# ImageProc.net
KiCad netlist of a schematic drawn in EAGLE
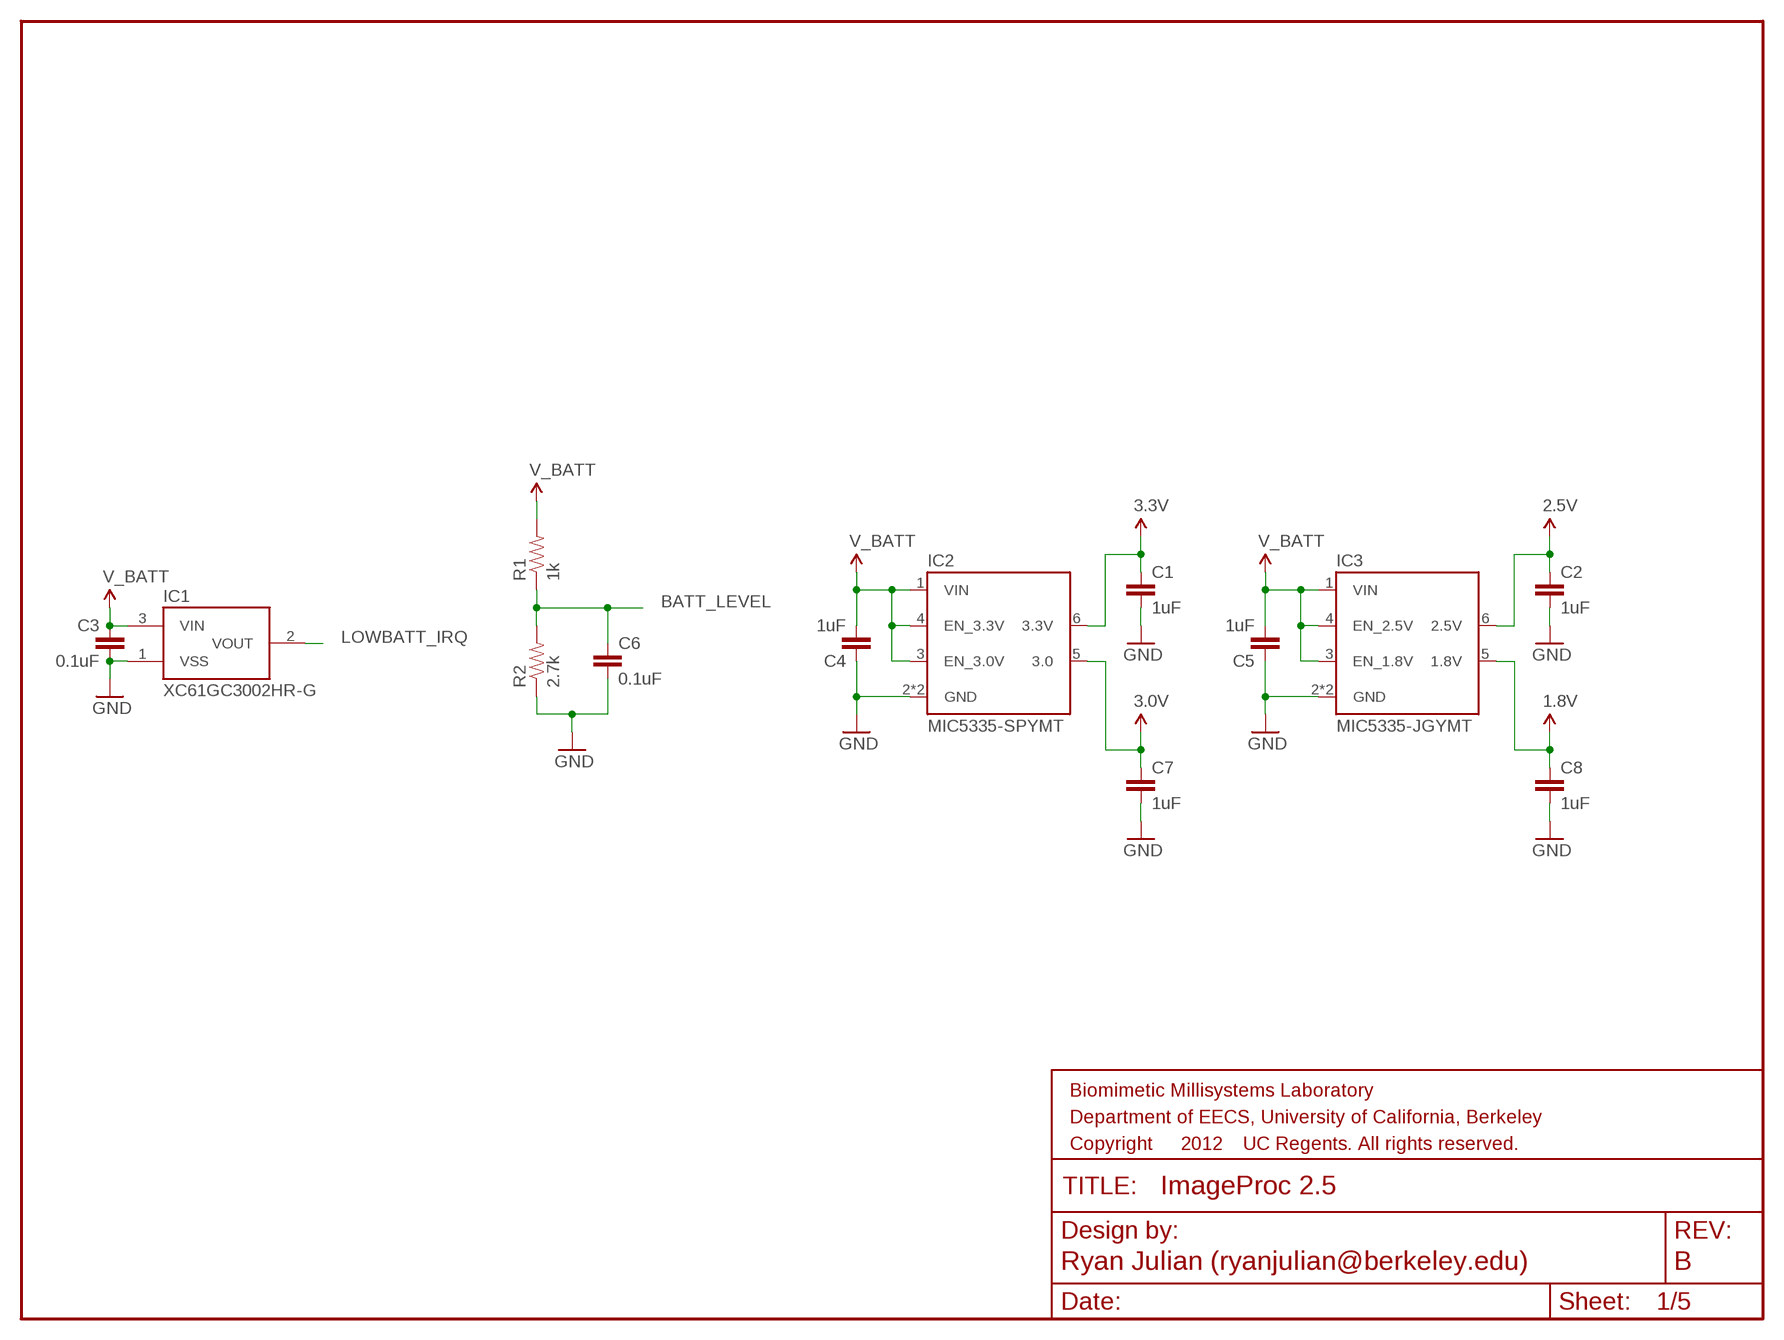
[diagram p0: schematic, sheet 1]
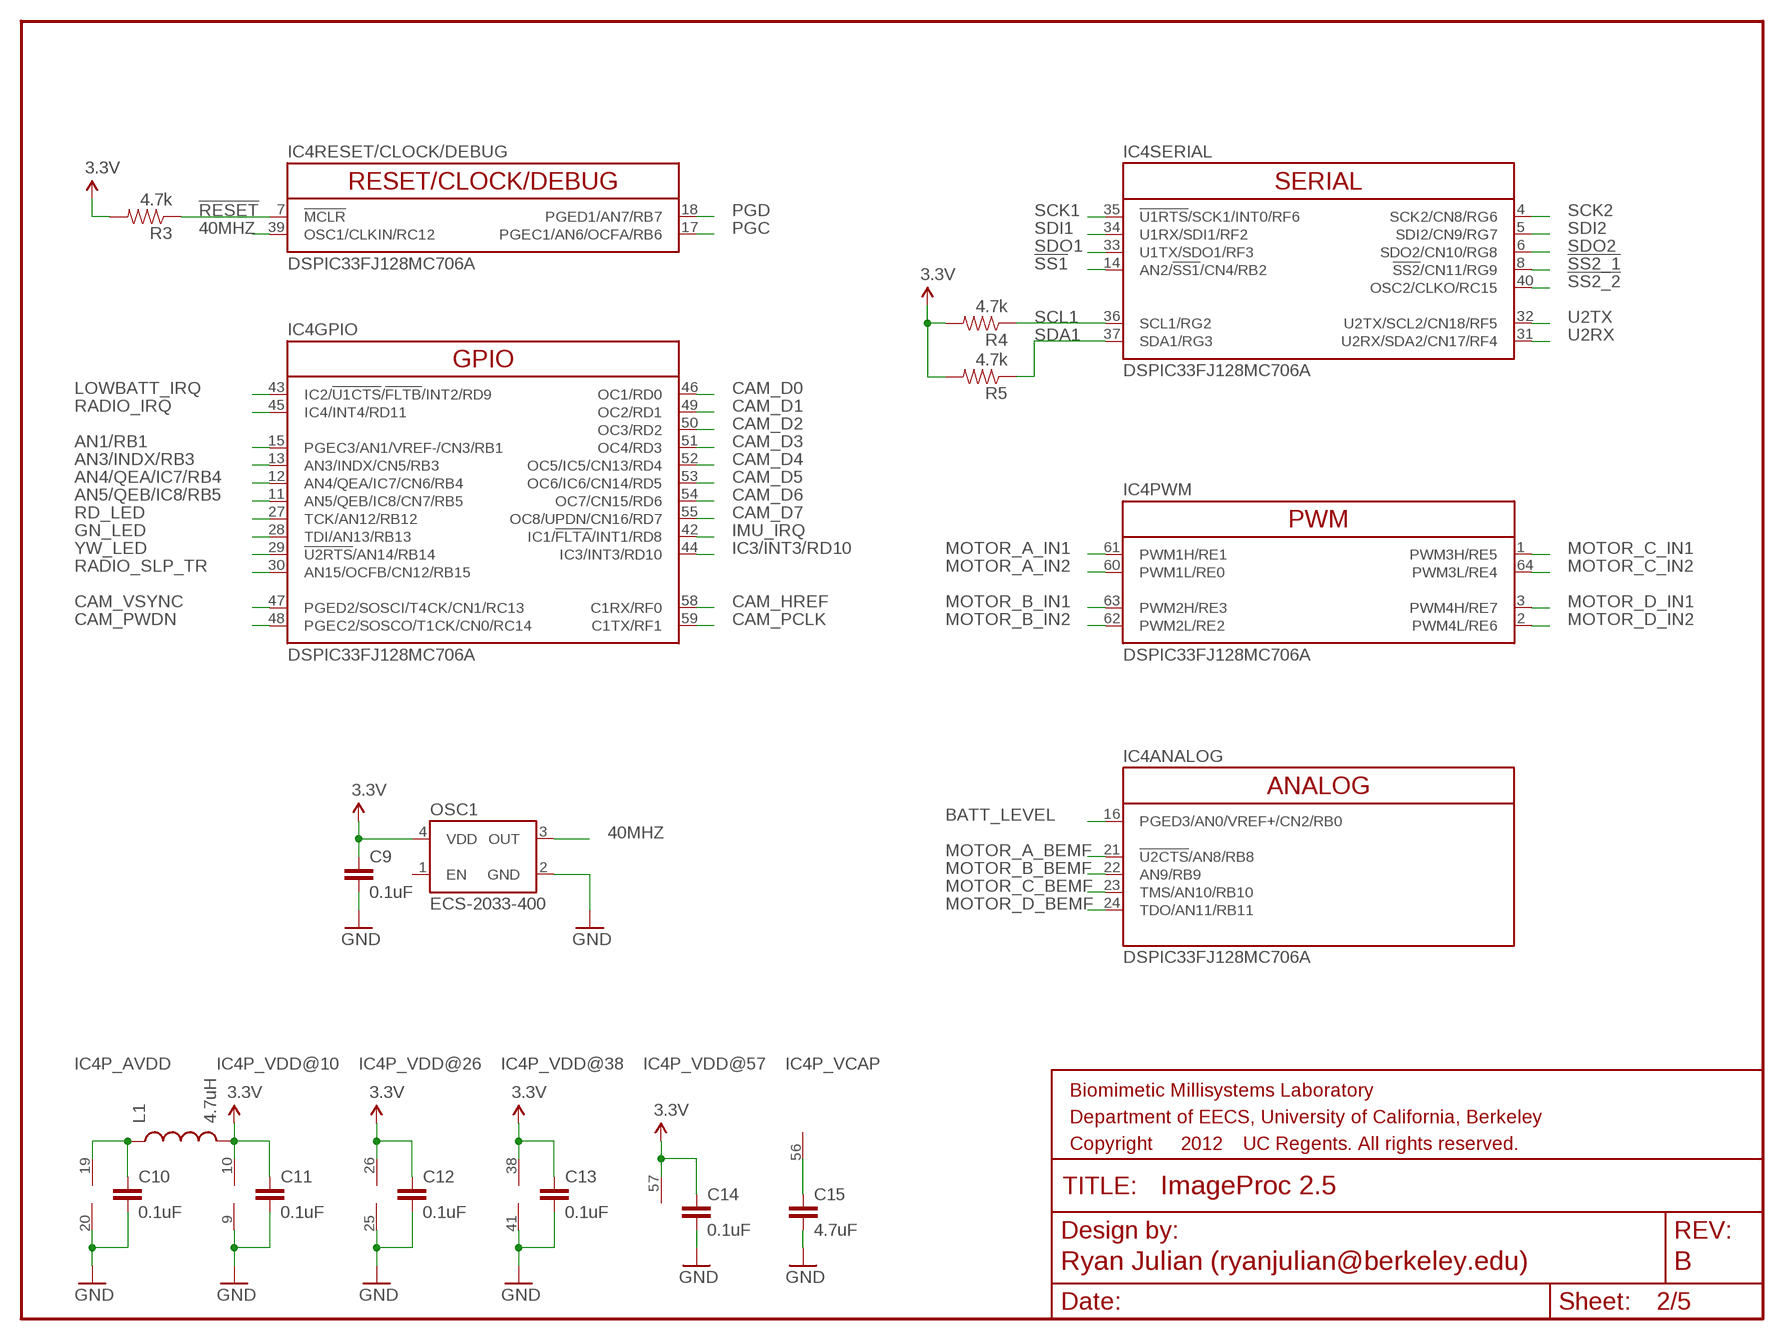
[diagram p1: schematic, sheet 2]
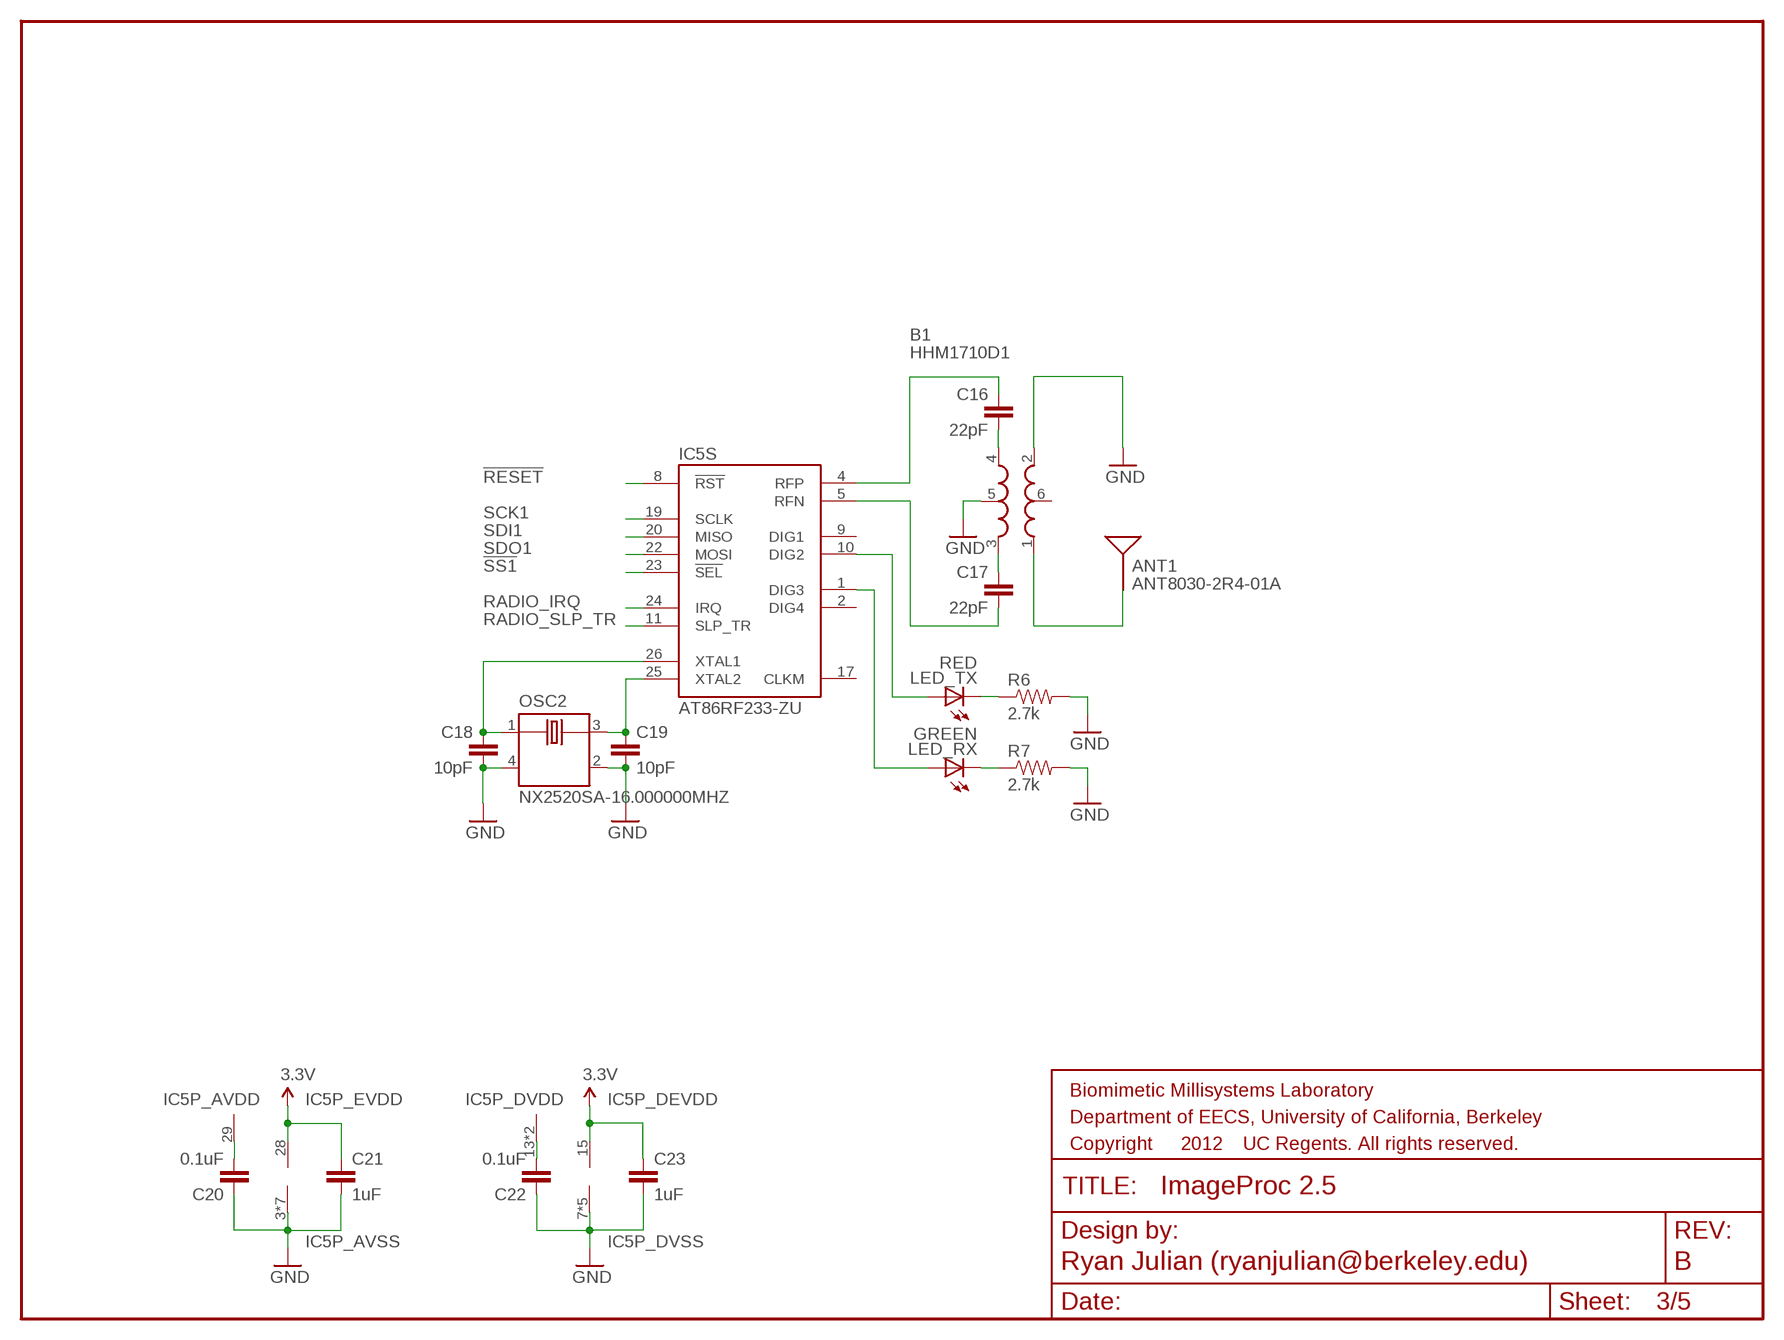
[diagram p2: schematic, sheet 3]
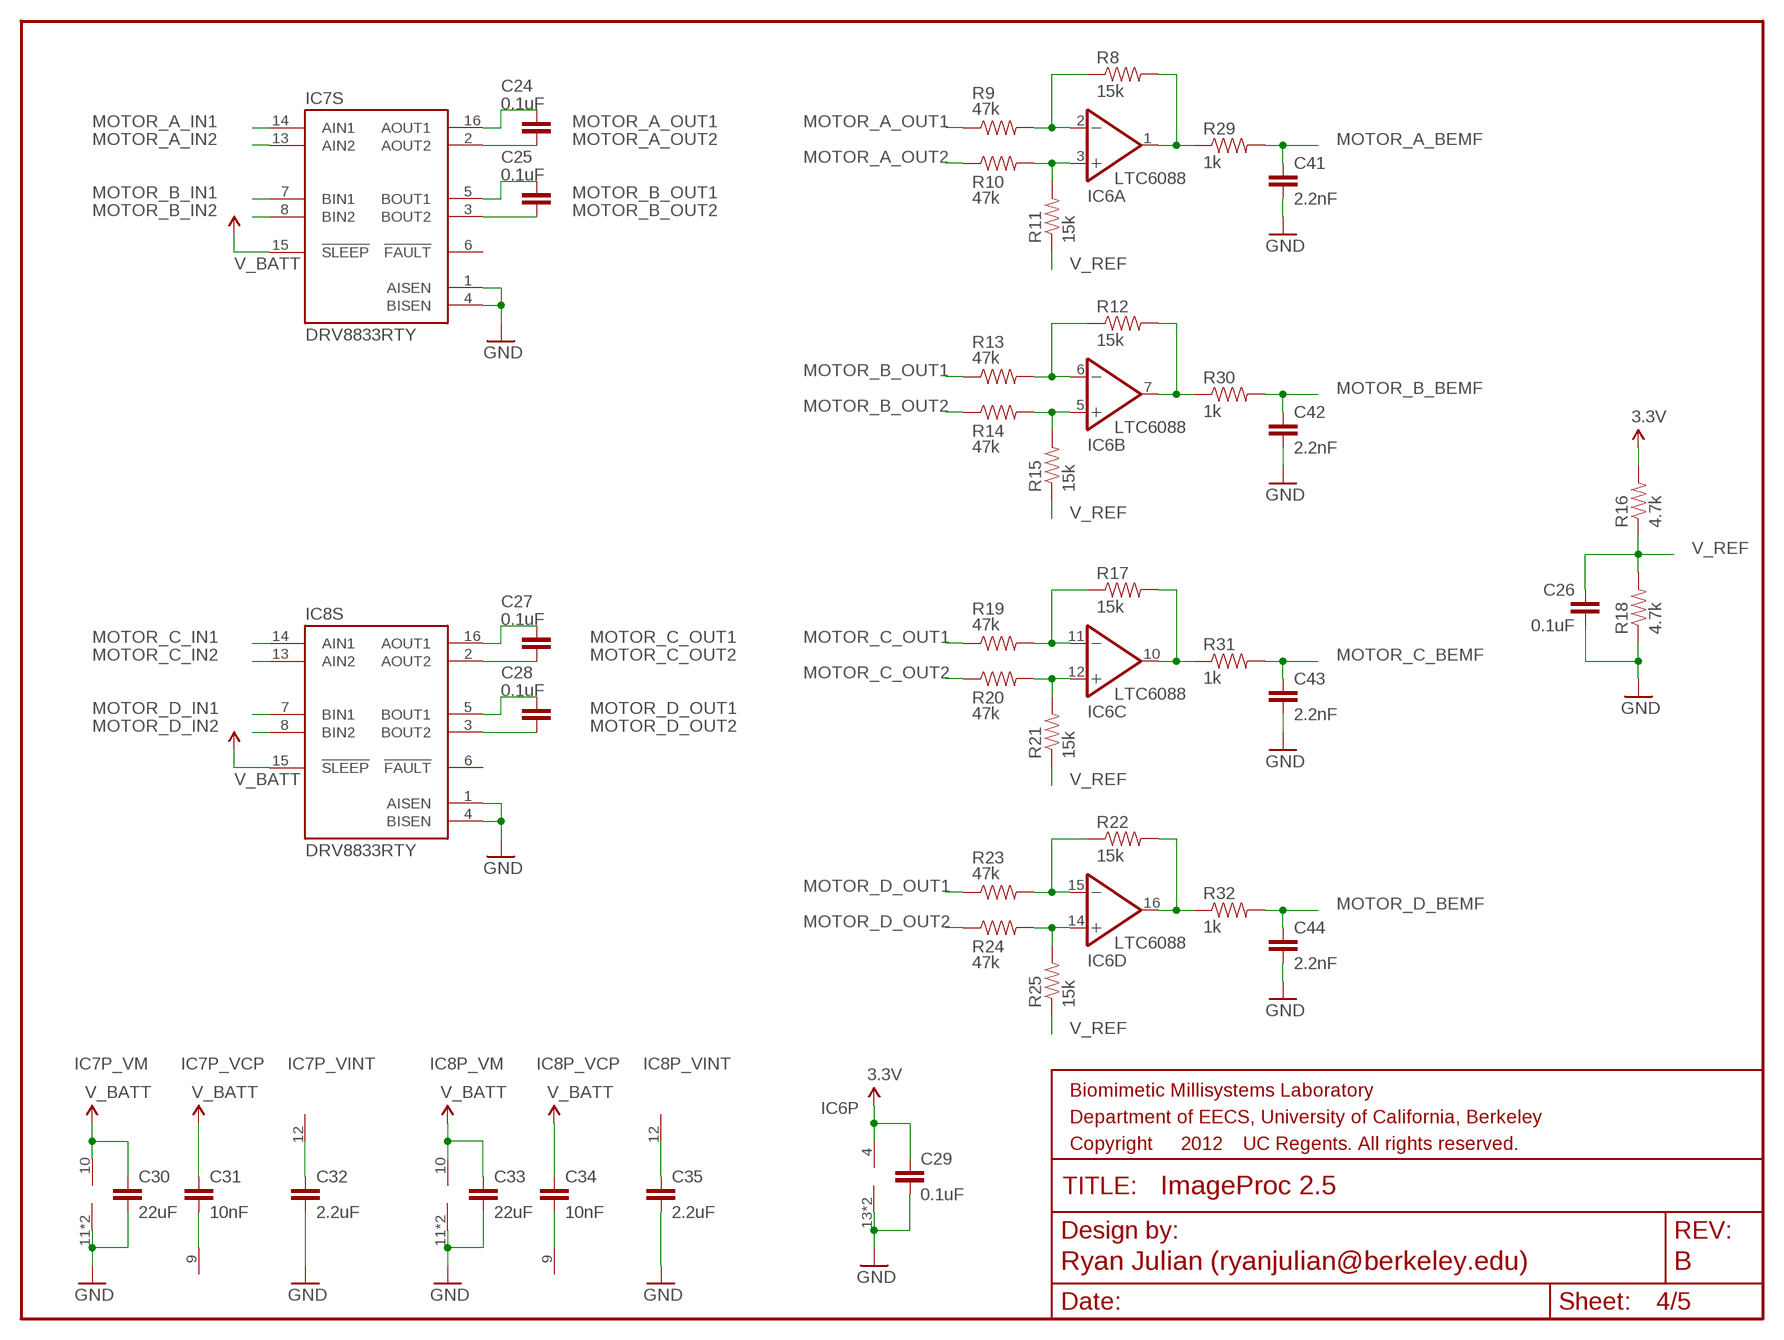
[diagram p3: schematic, sheet 4]
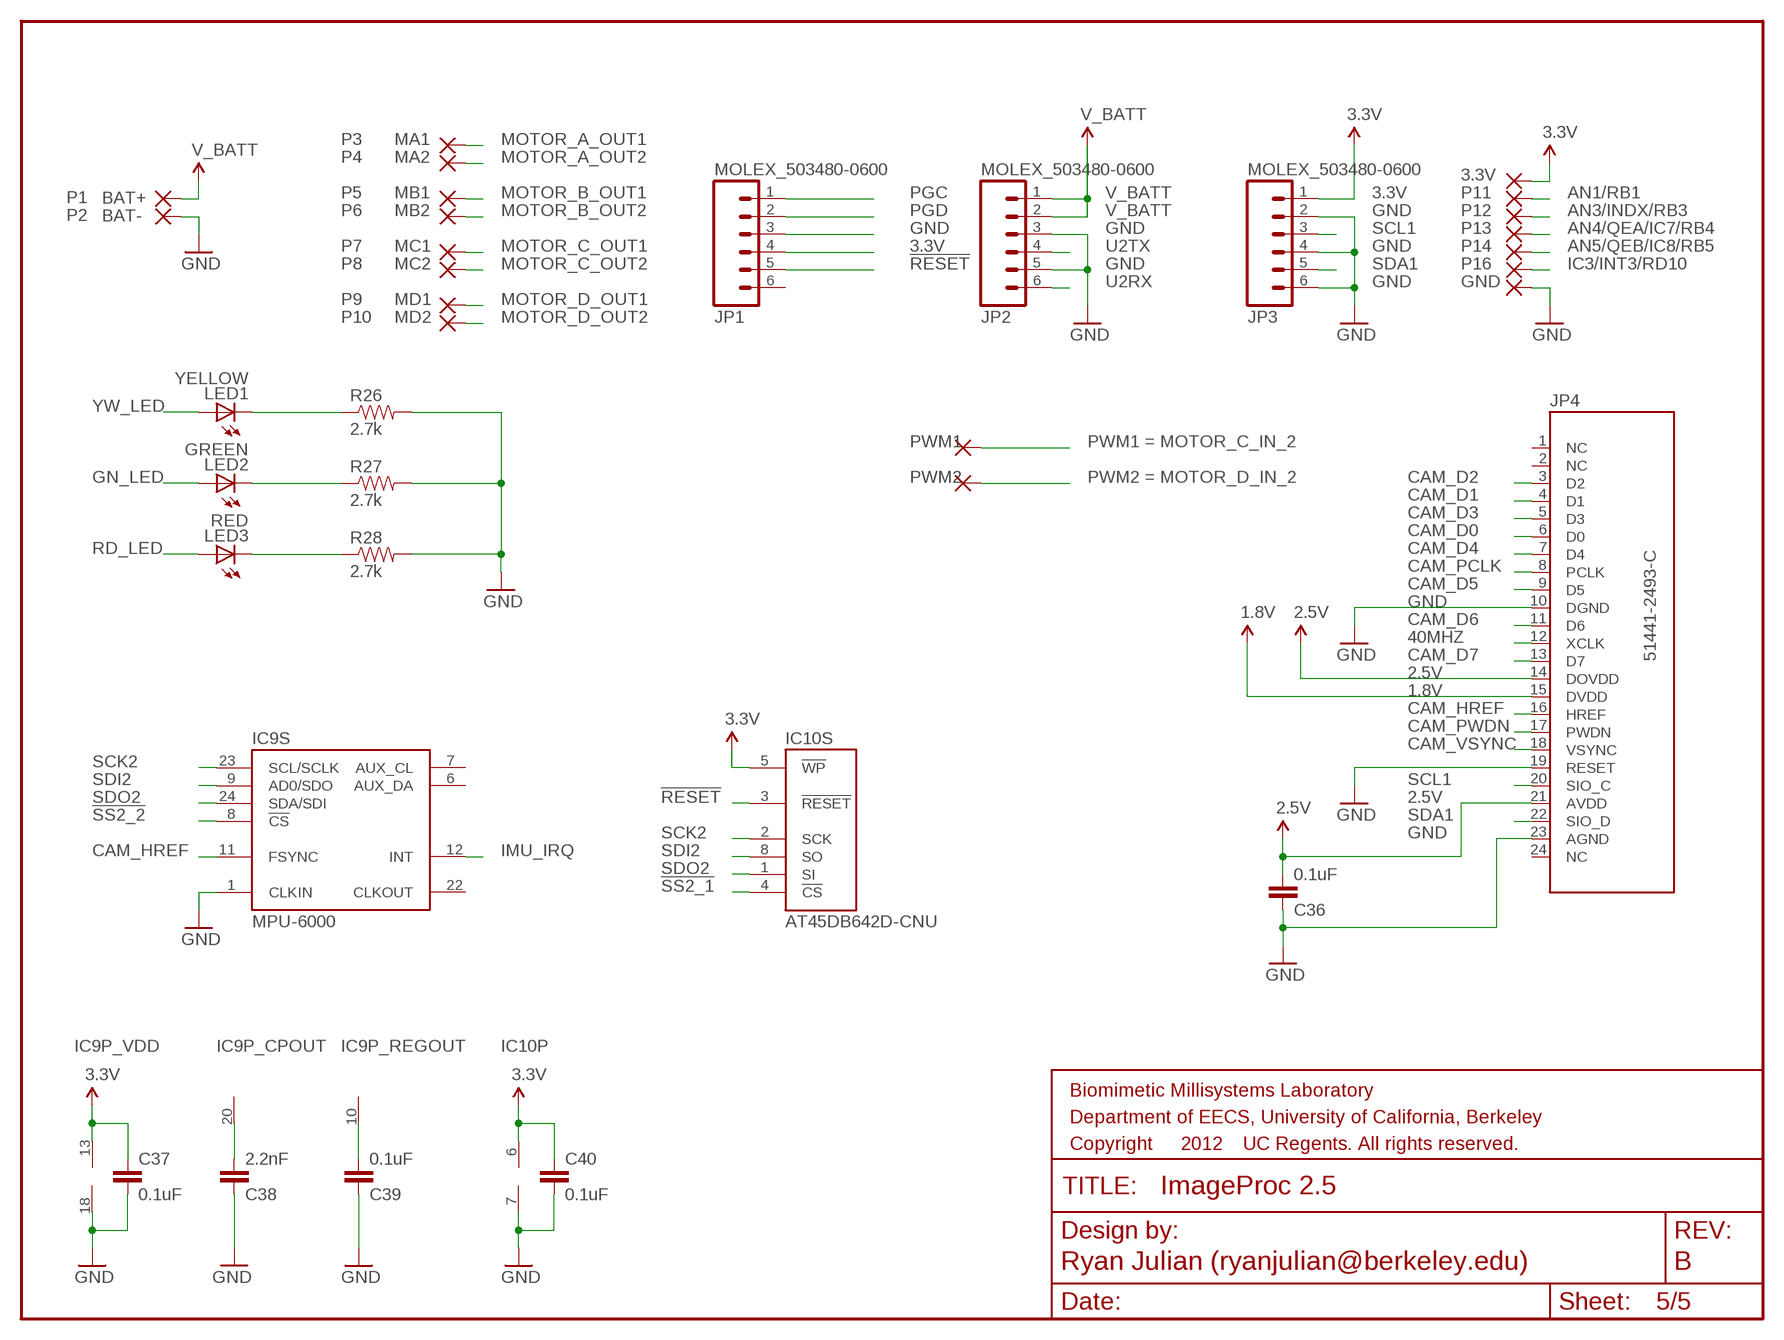
[diagram p4: schematic, sheet 5]

(export (version "E")
  (design (tool "Eeschema 10.0.6"))
  (components
    (comp (ref "3.3V")
      (value "EXT5")
      (footprint "eagle-import:SMD1,27-2,54")
      (libsource (lib "eagle-import") (part "SMD2"))
    )
    (comp (ref "C36")
      (value "0.1uF")
      (footprint "eagle-import:0402-CAP")
      (libsource (lib "eagle-import") (part "CAP0402-CAP"))
    )
    (comp (ref "C37")
      (value "0.1uF")
      (footprint "eagle-import:0402-CAP")
      (fields (field (name "TOLERANCE") "10%") (field (name "VOLTAGE") "4V"))
      (libsource (lib "eagle-import") (part "CAP0402-CAP"))
    )
    (comp (ref "C38")
      (value "2.2nF")
      (footprint "eagle-import:0402-CAP")
      (fields (field (name "TOLERANCE") "10%") (field (name "VOLTAGE") "50V"))
      (libsource (lib "eagle-import") (part "CAP0402-CAP"))
    )
    (comp (ref "C39")
      (value "0.1uF")
      (footprint "eagle-import:0402-CAP")
      (fields (field (name "TOLERANCE") "10%") (field (name "VOLTAGE") "2V"))
      (libsource (lib "eagle-import") (part "CAP0402-CAP"))
    )
    (comp (ref "C40")
      (value "0.1uF")
      (footprint "eagle-import:0402-CAP")
      (libsource (lib "eagle-import") (part "CAP0402-CAP"))
    )
    (comp (ref "GND")
      (value "EXT5")
      (footprint "eagle-import:SMD1,27-2,54")
      (libsource (lib "eagle-import") (part "SMD2"))
    )
    (comp (ref "IC9")
      (value "MPU-6000")
      (footprint "eagle-import:QFN-24")
      (libsource (lib "eagle-import") (part "MPU-6000"))
    )
    (comp (ref "IC10")
      (value "AT45DB642D-CNU")
      (footprint "eagle-import:CASON-8")
      (libsource (lib "eagle-import") (part "AT45DB642D-CNU"))
    )
    (comp (ref "JP1")
      (value "MOLEX_503480-0600")
      (footprint "eagle-import:MOLEX_503480-0600")
      (libsource (lib "eagle-import") (part "MOLEX_503480-0600"))
    )
    (comp (ref "JP2")
      (value "MOLEX_503480-0600")
      (footprint "eagle-import:MOLEX_503480-0600")
      (libsource (lib "eagle-import") (part "MOLEX_503480-0600"))
    )
    (comp (ref "JP3")
      (value "MOLEX_503480-0600")
      (footprint "eagle-import:MOLEX_503480-0600")
      (libsource (lib "eagle-import") (part "MOLEX_503480-0600"))
    )
    (comp (ref "JP4")
      (value "51441-2493-C")
      (footprint "eagle-import:MOLEX_52740-2490")
      (libsource (lib "eagle-import") (part "OV7660FSL_CON"))
    )
    (comp (ref "LED1")
      (value "YELLOW")
      (footprint "eagle-import:LED-0603")
      (libsource (lib "eagle-import") (part "LED0603"))
    )
    (comp (ref "LED2")
      (value "GREEN")
      (footprint "eagle-import:LED-0603")
      (libsource (lib "eagle-import") (part "LED0603"))
    )
    (comp (ref "LED3")
      (value "RED")
      (footprint "eagle-import:LED-0603")
      (libsource (lib "eagle-import") (part "LED0603"))
    )
    (comp (ref "P1")
      (value "BAT+")
      (footprint "eagle-import:SMD1,27-2,54")
      (libsource (lib "eagle-import") (part "SMD2"))
    )
    (comp (ref "P2")
      (value "BAT-")
      (footprint "eagle-import:SMD1,27-2,54")
      (libsource (lib "eagle-import") (part "SMD2"))
    )
    (comp (ref "P3")
      (value "MA1")
      (footprint "eagle-import:SMD1,27-2,54")
      (libsource (lib "eagle-import") (part "SMD2"))
    )
    (comp (ref "P4")
      (value "MA2")
      (footprint "eagle-import:SMD1,27-2,54")
      (libsource (lib "eagle-import") (part "SMD2"))
    )
    (comp (ref "P5")
      (value "MB1")
      (footprint "eagle-import:SMD1,27-2,54")
      (libsource (lib "eagle-import") (part "SMD2"))
    )
    (comp (ref "P6")
      (value "MB2")
      (footprint "eagle-import:SMD1,27-2,54")
      (libsource (lib "eagle-import") (part "SMD2"))
    )
    (comp (ref "P7")
      (value "MC1")
      (footprint "eagle-import:SMD1,27-2,54")
      (libsource (lib "eagle-import") (part "SMD2"))
    )
    (comp (ref "P8")
      (value "MC2")
      (footprint "eagle-import:SMD1,27-2,54")
      (libsource (lib "eagle-import") (part "SMD2"))
    )
    (comp (ref "P9")
      (value "MD1")
      (footprint "eagle-import:SMD1,27-2,54")
      (libsource (lib "eagle-import") (part "SMD2"))
    )
    (comp (ref "P10")
      (value "MD2")
      (footprint "eagle-import:SMD1,27-2,54")
      (libsource (lib "eagle-import") (part "SMD2"))
    )
    (comp (ref "P11")
      (value "EXT1")
      (footprint "eagle-import:SMD1,27-2,54")
      (libsource (lib "eagle-import") (part "SMD2"))
    )
    (comp (ref "P12")
      (value "EXT2")
      (footprint "eagle-import:SMD1,27-2,54")
      (libsource (lib "eagle-import") (part "SMD2"))
    )
    (comp (ref "P13")
      (value "EXT3")
      (footprint "eagle-import:SMD1,27-2,54")
      (libsource (lib "eagle-import") (part "SMD2"))
    )
    (comp (ref "P14")
      (value "EXT4")
      (footprint "eagle-import:SMD1,27-2,54")
      (libsource (lib "eagle-import") (part "SMD2"))
    )
    (comp (ref "P16")
      (value "EXT5")
      (footprint "eagle-import:SMD1,27-2,54")
      (libsource (lib "eagle-import") (part "SMD2"))
    )
    (comp (ref "PWM1")
      (value "EXT5")
      (footprint "eagle-import:SMD1,27-2,54")
      (fields (field (name "PWM1") "MOTOR_C_IN_2"))
      (libsource (lib "eagle-import") (part "SMD2"))
    )
    (comp (ref "PWM2")
      (value "EXT5")
      (footprint "eagle-import:SMD1,27-2,54")
      (fields (field (name "PWM2") "MOTOR_D_IN_2"))
      (libsource (lib "eagle-import") (part "SMD2"))
    )
    (comp (ref "R26")
      (value "2.7k")
      (footprint "eagle-import:0402-RES")
      (libsource (lib "eagle-import") (part "RESISTOR0402-RES"))
    )
    (comp (ref "R27")
      (value "2.7k")
      (footprint "eagle-import:0402-RES")
      (libsource (lib "eagle-import") (part "RESISTOR0402-RES"))
    )
    (comp (ref "R28")
      (value "2.7k")
      (footprint "eagle-import:0402-RES")
      (libsource (lib "eagle-import") (part "RESISTOR0402-RES"))
    )
    (comp (ref "C9")
      (value "0.1uF")
      (footprint "eagle-import:0402-CAP")
      (libsource (lib "eagle-import") (part "CAP0402-CAP"))
    )
    (comp (ref "C10")
      (value "0.1uF")
      (footprint "eagle-import:0402-CAP")
      (libsource (lib "eagle-import") (part "CAP0402-CAP"))
    )
    (comp (ref "C11")
      (value "0.1uF")
      (footprint "eagle-import:0402-CAP")
      (libsource (lib "eagle-import") (part "CAP0402-CAP"))
    )
    (comp (ref "C12")
      (value "0.1uF")
      (footprint "eagle-import:0402-CAP")
      (libsource (lib "eagle-import") (part "CAP0402-CAP"))
    )
    (comp (ref "C13")
      (value "0.1uF")
      (footprint "eagle-import:0402-CAP")
      (libsource (lib "eagle-import") (part "CAP0402-CAP"))
    )
    (comp (ref "C14")
      (value "0.1uF")
      (footprint "eagle-import:0402-CAP")
      (libsource (lib "eagle-import") (part "CAP0402-CAP"))
    )
    (comp (ref "C15")
      (value "4.7uF")
      (footprint "eagle-import:0603-CAP")
      (fields (field (name "COMMENT") "ESR < 5 Ohm") (field (name "VOLTAGE") "16V"))
      (libsource (lib "eagle-import") (part "CAP0603-CAP"))
    )
    (comp (ref "IC4")
      (value "DSPIC33FJ128MC706A")
      (footprint "eagle-import:TQFP-64")
      (libsource (lib "eagle-import") (part "DSPIC33FJ128MC706A"))
    )
    (comp (ref "L1")
      (value "4.7uH")
      (footprint "eagle-import:0603")
      (libsource (lib "eagle-import") (part "INDUCTOR0603"))
    )
    (comp (ref "OSC1")
      (value "ECS-2033-400")
      (footprint "eagle-import:OSCILLATOR-SMD")
      (libsource (lib "eagle-import") (part "ECS-2033-400"))
    )
    (comp (ref "R3")
      (value "4.7k")
      (footprint "eagle-import:0402-RES")
      (libsource (lib "eagle-import") (part "RESISTOR0402-RES"))
    )
    (comp (ref "R4")
      (value "4.7k")
      (footprint "eagle-import:0402-RES")
      (libsource (lib "eagle-import") (part "RESISTOR0402-RES"))
    )
    (comp (ref "R5")
      (value "4.7k")
      (footprint "eagle-import:0402-RES")
      (libsource (lib "eagle-import") (part "RESISTOR0402-RES"))
    )
    (comp (ref "ANT1")
      (value "ANT8030-2R4-01A")
      (footprint "eagle-import:ANT8030-2R4-01A")
      (libsource (lib "eagle-import") (part "ANT8030-2R4-01A"))
    )
    (comp (ref "B1")
      (value "HHM1710D1")
      (footprint "eagle-import:0603-BALUN")
      (libsource (lib "eagle-import") (part "HHM1710D1"))
    )
    (comp (ref "C16")
      (value "22pF")
      (footprint "eagle-import:0402-CAP")
      (fields (field (name "TOLERANCE") "5%") (field (name "VOLTAGE") "50V"))
      (libsource (lib "eagle-import") (part "CAP0402-CAP"))
    )
    (comp (ref "C17")
      (value "22pF")
      (footprint "eagle-import:0402-CAP")
      (fields (field (name "TOLERANCE") "5%") (field (name "VOLTAGE") "50V"))
      (libsource (lib "eagle-import") (part "CAP0402-CAP"))
    )
    (comp (ref "C18")
      (value "10pF")
      (footprint "eagle-import:0402-CAP")
      (fields (field (name "TOLERANCE") "10%") (field (name "VOLTAGE") "50V"))
      (libsource (lib "eagle-import") (part "CAP0402-CAP"))
    )
    (comp (ref "C19")
      (value "10pF")
      (footprint "eagle-import:0402-CAP")
      (fields (field (name "TOLERANCE") "10%") (field (name "VOLTAGE") "50V"))
      (libsource (lib "eagle-import") (part "CAP0402-CAP"))
    )
    (comp (ref "C20")
      (value "0.1uF")
      (footprint "eagle-import:0402-CAP")
      (fields (field (name "TOLERANCE") "10%") (field (name "VOLTAGE") "16V"))
      (libsource (lib "eagle-import") (part "CAP0402-CAP"))
    )
    (comp (ref "C21")
      (value "1uF")
      (footprint "eagle-import:0402-CAP")
      (fields (field (name "TOLERANCE") "10%") (field (name "VOLTAGE") "16V"))
      (libsource (lib "eagle-import") (part "CAP0402-CAP"))
    )
    (comp (ref "C22")
      (value "0.1uF")
      (footprint "eagle-import:0402-CAP")
      (fields (field (name "TOLERANCE") "10%") (field (name "VOLTAGE") "16V"))
      (libsource (lib "eagle-import") (part "CAP0402-CAP"))
    )
    (comp (ref "C23")
      (value "1uF")
      (footprint "eagle-import:0402-CAP")
      (fields (field (name "TOLERANCE") "10%") (field (name "VOLTAGE") "16V"))
      (libsource (lib "eagle-import") (part "CAP0402-CAP"))
    )
    (comp (ref "IC5")
      (value "AT86RF233-ZU")
      (footprint "eagle-import:VQFN-32QN2")
      (libsource (lib "eagle-import") (part "AT86RF233-ZU"))
    )
    (comp (ref "LED_RX")
      (value "GREEN")
      (footprint "eagle-import:LED-0603")
      (libsource (lib "eagle-import") (part "LED0603"))
    )
    (comp (ref "LED_TX")
      (value "RED")
      (footprint "eagle-import:LED-0603")
      (libsource (lib "eagle-import") (part "LED0603"))
    )
    (comp (ref "OSC2")
      (value "NX2520SA-16.000000MHZ")
      (footprint "eagle-import:CRYSTAL-SMD")
      (libsource (lib "eagle-import") (part "NX2520SA-16.000000MHZ"))
    )
    (comp (ref "R6")
      (value "2.7k")
      (footprint "eagle-import:0402-RES")
      (libsource (lib "eagle-import") (part "RESISTOR0402-RES"))
    )
    (comp (ref "R7")
      (value "2.7k")
      (footprint "eagle-import:0402-RES")
      (libsource (lib "eagle-import") (part "RESISTOR0402-RES"))
    )
    (comp (ref "C1")
      (value "1uF")
      (footprint "eagle-import:0402-CAP")
      (libsource (lib "eagle-import") (part "CAP0402-CAP"))
    )
    (comp (ref "C2")
      (value "1uF")
      (footprint "eagle-import:0402-CAP")
      (libsource (lib "eagle-import") (part "CAP0402-CAP"))
    )
    (comp (ref "C3")
      (value "0.1uF")
      (footprint "eagle-import:0402-CAP")
      (libsource (lib "eagle-import") (part "CAP0402-CAP"))
    )
    (comp (ref "C4")
      (value "1uF")
      (footprint "eagle-import:0402-CAP")
      (libsource (lib "eagle-import") (part "CAP0402-CAP"))
    )
    (comp (ref "C5")
      (value "1uF")
      (footprint "eagle-import:0402-CAP")
      (libsource (lib "eagle-import") (part "CAP0402-CAP"))
    )
    (comp (ref "C6")
      (value "0.1uF")
      (footprint "eagle-import:0402-CAP")
      (libsource (lib "eagle-import") (part "CAP0402-CAP"))
    )
    (comp (ref "C7")
      (value "1uF")
      (footprint "eagle-import:0402-CAP")
      (libsource (lib "eagle-import") (part "CAP0402-CAP"))
    )
    (comp (ref "C8")
      (value "1uF")
      (footprint "eagle-import:0402-CAP")
      (libsource (lib "eagle-import") (part "CAP0402-CAP"))
    )
    (comp (ref "IC1")
      (value "XC61GC3002HR-G")
      (footprint "eagle-import:USP-3")
      (libsource (lib "eagle-import") (part "XC61GC3002HR-G"))
    )
    (comp (ref "IC2")
      (value "MIC5335-SPYMT")
      (footprint "eagle-import:MLF-6")
      (libsource (lib "eagle-import") (part "MIC5335-SPYMT"))
    )
    (comp (ref "IC3")
      (value "MIC5335-JGYMT")
      (footprint "eagle-import:MLF-6")
      (libsource (lib "eagle-import") (part "MIC5335-JGYMT"))
    )
    (comp (ref "R1")
      (value "1k")
      (footprint "eagle-import:0402-RES")
      (libsource (lib "eagle-import") (part "RESISTOR0402-RES"))
    )
    (comp (ref "R2")
      (value "2.7k")
      (footprint "eagle-import:0402-RES")
      (libsource (lib "eagle-import") (part "RESISTOR0402-RES"))
    )
    (comp (ref "C24")
      (value "0.1uF")
      (footprint "eagle-import:0402-CAP")
      (fields (field (name "VOLTAGE") "10V"))
      (libsource (lib "eagle-import") (part "CAP0402-CAP"))
    )
    (comp (ref "C25")
      (value "0.1uF")
      (footprint "eagle-import:0402-CAP")
      (fields (field (name "VOLTAGE") "10V"))
      (libsource (lib "eagle-import") (part "CAP0402-CAP"))
    )
    (comp (ref "C26")
      (value "0.1uF")
      (footprint "eagle-import:0402-CAP")
      (libsource (lib "eagle-import") (part "CAP0402-CAP"))
    )
    (comp (ref "C27")
      (value "0.1uF")
      (footprint "eagle-import:0402-CAP")
      (fields (field (name "VOLTAGE") "10V"))
      (libsource (lib "eagle-import") (part "CAP0402-CAP"))
    )
    (comp (ref "C28")
      (value "0.1uF")
      (footprint "eagle-import:0402-CAP")
      (fields (field (name "VOLTAGE") "10V"))
      (libsource (lib "eagle-import") (part "CAP0402-CAP"))
    )
    (comp (ref "C29")
      (value "0.1uF")
      (footprint "eagle-import:0402-CAP")
      (libsource (lib "eagle-import") (part "CAP0402-CAP"))
    )
    (comp (ref "C30")
      (value "22uF")
      (footprint "eagle-import:0603-CAP")
      (libsource (lib "eagle-import") (part "CAP0603-CAP"))
    )
    (comp (ref "C31")
      (value "10nF")
      (footprint "eagle-import:0402-CAP")
      (fields (field (name "VOLTAGE") "16V"))
      (libsource (lib "eagle-import") (part "CAP0402-CAP"))
    )
    (comp (ref "C32")
      (value "2.2uF")
      (footprint "eagle-import:0402-CAP")
      (fields (field (name "VOLTAGE") "6.3V"))
      (libsource (lib "eagle-import") (part "CAP0402-CAP"))
    )
    (comp (ref "C33")
      (value "22uF")
      (footprint "eagle-import:0603-CAP")
      (libsource (lib "eagle-import") (part "CAP0603-CAP"))
    )
    (comp (ref "C34")
      (value "10nF")
      (footprint "eagle-import:0402-CAP")
      (fields (field (name "VOLTAGE") "16V"))
      (libsource (lib "eagle-import") (part "CAP0402-CAP"))
    )
    (comp (ref "C35")
      (value "2.2uF")
      (footprint "eagle-import:0402-CAP")
      (fields (field (name "VOLTAGE") "6.3V"))
      (libsource (lib "eagle-import") (part "CAP0402-CAP"))
    )
    (comp (ref "C41")
      (value "2.2nF")
      (footprint "eagle-import:0402-CAP")
      (libsource (lib "eagle-import") (part "CAP0402-CAP"))
    )
    (comp (ref "C42")
      (value "2.2nF")
      (footprint "eagle-import:0402-CAP")
      (libsource (lib "eagle-import") (part "CAP0402-CAP"))
    )
    (comp (ref "C43")
      (value "2.2nF")
      (footprint "eagle-import:0402-CAP")
      (libsource (lib "eagle-import") (part "CAP0402-CAP"))
    )
    (comp (ref "C44")
      (value "2.2nF")
      (footprint "eagle-import:0402-CAP")
      (libsource (lib "eagle-import") (part "CAP0402-CAP"))
    )
    (comp (ref "IC6")
      (value "LTC6088")
      (footprint "eagle-import:DFN-16")
      (libsource (lib "eagle-import") (part "LTC6088"))
    )
    (comp (ref "IC7")
      (value "DRV8833RTY")
      (footprint "eagle-import:S-PWQFN-N16")
      (libsource (lib "eagle-import") (part "DRV8833RTY"))
    )
    (comp (ref "IC8")
      (value "DRV8833RTY")
      (footprint "eagle-import:S-PWQFN-N16")
      (libsource (lib "eagle-import") (part "DRV8833RTY"))
    )
    (comp (ref "R8")
      (value "15k")
      (footprint "eagle-import:0402-RES")
      (fields (field (name "TOLERANCE") "1%"))
      (libsource (lib "eagle-import") (part "RESISTOR0402-RES"))
    )
    (comp (ref "R9")
      (value "47k")
      (footprint "eagle-import:0402-RES")
      (fields (field (name "TOLERANCE") "1%"))
      (libsource (lib "eagle-import") (part "RESISTOR0402-RES"))
    )
    (comp (ref "R10")
      (value "47k")
      (footprint "eagle-import:0402-RES")
      (fields (field (name "TOLERANCE") "1%"))
      (libsource (lib "eagle-import") (part "RESISTOR0402-RES"))
    )
    (comp (ref "R11")
      (value "15k")
      (footprint "eagle-import:0402-RES")
      (fields (field (name "TOLERANCE") "1%"))
      (libsource (lib "eagle-import") (part "RESISTOR0402-RES"))
    )
    (comp (ref "R12")
      (value "15k")
      (footprint "eagle-import:0402-RES")
      (fields (field (name "TOLERANCE") "1%"))
      (libsource (lib "eagle-import") (part "RESISTOR0402-RES"))
    )
    (comp (ref "R13")
      (value "47k")
      (footprint "eagle-import:0402-RES")
      (fields (field (name "TOLERANCE") "1%"))
      (libsource (lib "eagle-import") (part "RESISTOR0402-RES"))
    )
    (comp (ref "R14")
      (value "47k")
      (footprint "eagle-import:0402-RES")
      (fields (field (name "TOLERANCE") "1%"))
      (libsource (lib "eagle-import") (part "RESISTOR0402-RES"))
    )
    (comp (ref "R15")
      (value "15k")
      (footprint "eagle-import:0402-RES")
      (fields (field (name "TOLERANCE") "1%"))
      (libsource (lib "eagle-import") (part "RESISTOR0402-RES"))
    )
    (comp (ref "R16")
      (value "4.7k")
      (footprint "eagle-import:0402-RES")
      (fields (field (name "TOLERANCE") "1%"))
      (libsource (lib "eagle-import") (part "RESISTOR0402-RES"))
    )
    (comp (ref "R17")
      (value "15k")
      (footprint "eagle-import:0402-RES")
      (fields (field (name "TOLERANCE") "1%"))
      (libsource (lib "eagle-import") (part "RESISTOR0402-RES"))
    )
    (comp (ref "R18")
      (value "4.7k")
      (footprint "eagle-import:0402-RES")
      (fields (field (name "TOLERANCE") "1%"))
      (libsource (lib "eagle-import") (part "RESISTOR0402-RES"))
    )
    (comp (ref "R19")
      (value "47k")
      (footprint "eagle-import:0402-RES")
      (fields (field (name "TOLERANCE") "1%"))
      (libsource (lib "eagle-import") (part "RESISTOR0402-RES"))
    )
    (comp (ref "R20")
      (value "47k")
      (footprint "eagle-import:0402-RES")
      (fields (field (name "TOLERANCE") "1%"))
      (libsource (lib "eagle-import") (part "RESISTOR0402-RES"))
    )
    (comp (ref "R21")
      (value "15k")
      (footprint "eagle-import:0402-RES")
      (fields (field (name "TOLERANCE") "1%"))
      (libsource (lib "eagle-import") (part "RESISTOR0402-RES"))
    )
    (comp (ref "R22")
      (value "15k")
      (footprint "eagle-import:0402-RES")
      (fields (field (name "TOLERANCE") "1%"))
      (libsource (lib "eagle-import") (part "RESISTOR0402-RES"))
    )
    (comp (ref "R23")
      (value "47k")
      (footprint "eagle-import:0402-RES")
      (fields (field (name "TOLERANCE") "1%"))
      (libsource (lib "eagle-import") (part "RESISTOR0402-RES"))
    )
    (comp (ref "R24")
      (value "47k")
      (footprint "eagle-import:0402-RES")
      (fields (field (name "TOLERANCE") "1%"))
      (libsource (lib "eagle-import") (part "RESISTOR0402-RES"))
    )
    (comp (ref "R25")
      (value "15k")
      (footprint "eagle-import:0402-RES")
      (fields (field (name "TOLERANCE") "1%"))
      (libsource (lib "eagle-import") (part "RESISTOR0402-RES"))
    )
    (comp (ref "R29")
      (value "1k")
      (footprint "eagle-import:0402-RES")
      (libsource (lib "eagle-import") (part "RESISTOR0402-RES"))
    )
    (comp (ref "R30")
      (value "1k")
      (footprint "eagle-import:0402-RES")
      (libsource (lib "eagle-import") (part "RESISTOR0402-RES"))
    )
    (comp (ref "R31")
      (value "1k")
      (footprint "eagle-import:0402-RES")
      (libsource (lib "eagle-import") (part "RESISTOR0402-RES"))
    )
    (comp (ref "R32")
      (value "1k")
      (footprint "eagle-import:0402-RES")
      (libsource (lib "eagle-import") (part "RESISTOR0402-RES"))
    )
  )
  (nets
    (net (code "1") (name "1.8V") (class "Default")
      (node (ref "C8") (pin "1") (pinfunction "1_1") (pintype "passive"))
      (node (ref "IC3") (pin "5") (pinfunction "1.8V_5") (pintype "bidirectional"))
      (node (ref "JP4") (pin "15") (pinfunction "DVDD_15") (pintype "bidirectional"))
    )
    (net (code "2") (name "2.5V") (class "Default")
      (node (ref "C2") (pin "1") (pinfunction "1_1") (pintype "passive"))
      (node (ref "C36") (pin "2") (pinfunction "2_2") (pintype "passive"))
      (node (ref "IC3") (pin "6") (pinfunction "2.5V_6") (pintype "bidirectional"))
      (node (ref "JP4") (pin "14") (pinfunction "DOVDD_14") (pintype "bidirectional"))
      (node (ref "JP4") (pin "21") (pinfunction "AVDD_21") (pintype "bidirectional"))
    )
    (net (code "3") (name "3.0V") (class "Default")
      (node (ref "C7") (pin "1") (pinfunction "1_1") (pintype "passive"))
      (node (ref "IC2") (pin "5") (pinfunction "3.0_5") (pintype "bidirectional"))
    )
    (net (code "4") (name "3.3V") (class "Default")
      (node (ref "3.3V") (pin "1") (pinfunction "P_1") (pintype "passive"))
      (node (ref "C1") (pin "1") (pinfunction "1_1") (pintype "passive"))
      (node (ref "C11") (pin "1") (pinfunction "1_1") (pintype "passive"))
      (node (ref "C12") (pin "1") (pinfunction "1_1") (pintype "passive"))
      (node (ref "C13") (pin "1") (pinfunction "1_1") (pintype "passive"))
      (node (ref "C14") (pin "1") (pinfunction "1_1") (pintype "passive"))
      (node (ref "C21") (pin "1") (pinfunction "1_1") (pintype "passive"))
      (node (ref "C23") (pin "1") (pinfunction "1_1") (pintype "passive"))
      (node (ref "C29") (pin "1") (pinfunction "1_1") (pintype "passive"))
      (node (ref "C37") (pin "1") (pinfunction "1_1") (pintype "passive"))
      (node (ref "C40") (pin "1") (pinfunction "1_1") (pintype "passive"))
      (node (ref "C9") (pin "1") (pinfunction "1_1") (pintype "passive"))
      (node (ref "IC10") (pin "5") (pinfunction "~{WP}_5") (pintype "bidirectional"))
      (node (ref "IC10") (pin "6") (pinfunction "V+_6") (pintype "power_in"))
      (node (ref "IC2") (pin "6") (pinfunction "3.3V_6") (pintype "bidirectional"))
      (node (ref "IC4") (pin "10") (pinfunction "V+_10") (pintype "power_in"))
      (node (ref "IC4") (pin "26") (pinfunction "V+_26") (pintype "power_in"))
      (node (ref "IC4") (pin "38") (pinfunction "V+_38") (pintype "power_in"))
      (node (ref "IC4") (pin "57") (pinfunction "V+_57") (pintype "power_in"))
      (node (ref "IC5") (pin "15") (pinfunction "V+_15") (pintype "power_in"))
      (node (ref "IC5") (pin "28") (pinfunction "V+_28") (pintype "power_in"))
      (node (ref "IC6") (pin "4") (pinfunction "V+_4") (pintype "power_in"))
      (node (ref "IC9") (pin "13") (pinfunction "V+_13") (pintype "power_in"))
      (node (ref "JP1") (pin "4") (pinfunction "4_4") (pintype "passive"))
      (node (ref "JP3") (pin "1") (pinfunction "1_1") (pintype "passive"))
      (node (ref "L1") (pin "2") (pinfunction "2_2") (pintype "passive"))
      (node (ref "OSC1") (pin "4") (pinfunction "VDD_4") (pintype "bidirectional"))
      (node (ref "R16") (pin "2") (pinfunction "2_2") (pintype "passive"))
      (node (ref "R3") (pin "2") (pinfunction "2_2") (pintype "passive"))
      (node (ref "R4") (pin "2") (pinfunction "2_2") (pintype "passive"))
      (node (ref "R5") (pin "2") (pinfunction "2_2") (pintype "passive"))
    )
    (net (code "5") (name "40MHZ") (class "Default")
      (node (ref "IC4") (pin "39") (pinfunction "OSC1/CLKIN/RC12_39") (pintype "bidirectional"))
      (node (ref "JP4") (pin "12") (pinfunction "XCLK_12") (pintype "bidirectional"))
      (node (ref "OSC1") (pin "3") (pinfunction "OUT_3") (pintype "bidirectional"))
    )
    (net (code "6") (name "AN1{slash}RB1") (class "Default")
      (node (ref "IC4") (pin "15") (pinfunction "PGEC3/AN1/VREF-/CN3/RB1_15") (pintype "bidirectional"))
      (node (ref "P11") (pin "1") (pinfunction "P_1") (pintype "passive"))
    )
    (net (code "7") (name "AN3{slash}INDX{slash}RB3") (class "Default")
      (node (ref "IC4") (pin "13") (pinfunction "AN3/INDX/CN5/RB3_13") (pintype "bidirectional"))
      (node (ref "P12") (pin "1") (pinfunction "P_1") (pintype "passive"))
    )
    (net (code "8") (name "AN4{slash}QEA{slash}IC7{slash}RB4") (class "Default")
      (node (ref "IC4") (pin "12") (pinfunction "AN4/QEA/IC7/CN6/RB4_12") (pintype "bidirectional"))
      (node (ref "P13") (pin "1") (pinfunction "P_1") (pintype "passive"))
    )
    (net (code "9") (name "AN5{slash}QEB{slash}IC8{slash}RB5") (class "Default")
      (node (ref "IC4") (pin "11") (pinfunction "AN5/QEB/IC8/CN7/RB5_11") (pintype "bidirectional"))
      (node (ref "P14") (pin "1") (pinfunction "P_1") (pintype "passive"))
    )
    (net (code "10") (name "BATT_LEVEL") (class "Default")
      (node (ref "C6") (pin "1") (pinfunction "1_1") (pintype "passive"))
      (node (ref "IC4") (pin "16") (pinfunction "PGED3/AN0/VREF+/CN2/RB0_16") (pintype "bidirectional"))
      (node (ref "R1") (pin "1") (pinfunction "1_1") (pintype "passive"))
      (node (ref "R2") (pin "2") (pinfunction "2_2") (pintype "passive"))
    )
    (net (code "11") (name "CAM_D0") (class "Default")
      (node (ref "IC4") (pin "46") (pinfunction "OC1/RD0_46") (pintype "bidirectional"))
      (node (ref "JP4") (pin "6") (pinfunction "D0_6") (pintype "bidirectional"))
    )
    (net (code "12") (name "CAM_D1") (class "Default")
      (node (ref "IC4") (pin "49") (pinfunction "OC2/RD1_49") (pintype "bidirectional"))
      (node (ref "JP4") (pin "4") (pinfunction "D1_4") (pintype "bidirectional"))
    )
    (net (code "13") (name "CAM_D2") (class "Default")
      (node (ref "IC4") (pin "50") (pinfunction "OC3/RD2_50") (pintype "bidirectional"))
      (node (ref "JP4") (pin "3") (pinfunction "D2_3") (pintype "bidirectional"))
    )
    (net (code "14") (name "CAM_D3") (class "Default")
      (node (ref "IC4") (pin "51") (pinfunction "OC4/RD3_51") (pintype "bidirectional"))
      (node (ref "JP4") (pin "5") (pinfunction "D3_5") (pintype "bidirectional"))
    )
    (net (code "15") (name "CAM_D4") (class "Default")
      (node (ref "IC4") (pin "52") (pinfunction "OC5/IC5/CN13/RD4_52") (pintype "bidirectional"))
      (node (ref "JP4") (pin "7") (pinfunction "D4_7") (pintype "bidirectional"))
    )
    (net (code "16") (name "CAM_D5") (class "Default")
      (node (ref "IC4") (pin "53") (pinfunction "OC6/IC6/CN14/RD5_53") (pintype "bidirectional"))
      (node (ref "JP4") (pin "9") (pinfunction "D5_9") (pintype "bidirectional"))
    )
    (net (code "17") (name "CAM_D6") (class "Default")
      (node (ref "IC4") (pin "54") (pinfunction "OC7/CN15/RD6_54") (pintype "bidirectional"))
      (node (ref "JP4") (pin "11") (pinfunction "D6_11") (pintype "bidirectional"))
    )
    (net (code "18") (name "CAM_D7") (class "Default")
      (node (ref "IC4") (pin "55") (pinfunction "OC8/UPDN/CN16/RD7_55") (pintype "bidirectional"))
      (node (ref "JP4") (pin "13") (pinfunction "D7_13") (pintype "bidirectional"))
    )
    (net (code "19") (name "CAM_HREF") (class "Default")
      (node (ref "IC4") (pin "58") (pinfunction "C1RX/RF0_58") (pintype "bidirectional"))
      (node (ref "IC9") (pin "11") (pinfunction "FSYNC_11") (pintype "bidirectional"))
      (node (ref "JP4") (pin "16") (pinfunction "HREF_16") (pintype "bidirectional"))
    )
    (net (code "20") (name "CAM_PCLK") (class "Default")
      (node (ref "IC4") (pin "59") (pinfunction "C1TX/RF1_59") (pintype "bidirectional"))
      (node (ref "JP4") (pin "8") (pinfunction "PCLK_8") (pintype "bidirectional"))
    )
    (net (code "21") (name "CAM_PWDN") (class "Default")
      (node (ref "IC4") (pin "48") (pinfunction "PGEC2/SOSCO/T1CK/CN0/RC14_48") (pintype "bidirectional"))
      (node (ref "JP4") (pin "17") (pinfunction "PWDN_17") (pintype "bidirectional"))
    )
    (net (code "22") (name "CAM_VSYNC") (class "Default")
      (node (ref "IC4") (pin "47") (pinfunction "PGED2/SOSCI/T4CK/CN1/RC13_47") (pintype "bidirectional"))
      (node (ref "JP4") (pin "18") (pinfunction "VSYNC_18") (pintype "bidirectional"))
    )
    (net (code "23") (name "GND") (class "Default")
      (node (ref "B1") (pin "2") (pinfunction "RFGND_2") (pintype "bidirectional"))
      (node (ref "B1") (pin "5") (pinfunction "GND_5") (pintype "bidirectional"))
      (node (ref "C1") (pin "2") (pinfunction "2_2") (pintype "passive"))
      (node (ref "C10") (pin "2") (pinfunction "2_2") (pintype "passive"))
      (node (ref "C11") (pin "2") (pinfunction "2_2") (pintype "passive"))
      (node (ref "C12") (pin "2") (pinfunction "2_2") (pintype "passive"))
      (node (ref "C13") (pin "2") (pinfunction "2_2") (pintype "passive"))
      (node (ref "C14") (pin "2") (pinfunction "2_2") (pintype "passive"))
      (node (ref "C15") (pin "2") (pinfunction "2_2") (pintype "passive"))
      (node (ref "C18") (pin "2") (pinfunction "2_2") (pintype "passive"))
      (node (ref "C19") (pin "2") (pinfunction "2_2") (pintype "passive"))
      (node (ref "C2") (pin "2") (pinfunction "2_2") (pintype "passive"))
      (node (ref "C20") (pin "1") (pinfunction "1_1") (pintype "passive"))
      (node (ref "C21") (pin "2") (pinfunction "2_2") (pintype "passive"))
      (node (ref "C22") (pin "1") (pinfunction "1_1") (pintype "passive"))
      (node (ref "C23") (pin "2") (pinfunction "2_2") (pintype "passive"))
      (node (ref "C26") (pin "2") (pinfunction "2_2") (pintype "passive"))
      (node (ref "C29") (pin "2") (pinfunction "2_2") (pintype "passive"))
      (node (ref "C3") (pin "2") (pinfunction "2_2") (pintype "passive"))
      (node (ref "C30") (pin "2") (pinfunction "2_2") (pintype "passive"))
      (node (ref "C32") (pin "2") (pinfunction "2_2") (pintype "passive"))
      (node (ref "C33") (pin "2") (pinfunction "2_2") (pintype "passive"))
      (node (ref "C35") (pin "2") (pinfunction "2_2") (pintype "passive"))
      (node (ref "C36") (pin "1") (pinfunction "1_1") (pintype "passive"))
      (node (ref "C37") (pin "2") (pinfunction "2_2") (pintype "passive"))
      (node (ref "C38") (pin "1") (pinfunction "1_1") (pintype "passive"))
      (node (ref "C39") (pin "1") (pinfunction "1_1") (pintype "passive"))
      (node (ref "C4") (pin "1") (pinfunction "1_1") (pintype "passive"))
      (node (ref "C40") (pin "2") (pinfunction "2_2") (pintype "passive"))
      (node (ref "C41") (pin "2") (pinfunction "2_2") (pintype "passive"))
      (node (ref "C42") (pin "2") (pinfunction "2_2") (pintype "passive"))
      (node (ref "C43") (pin "2") (pinfunction "2_2") (pintype "passive"))
      (node (ref "C44") (pin "2") (pinfunction "2_2") (pintype "passive"))
      (node (ref "C5") (pin "1") (pinfunction "1_1") (pintype "passive"))
      (node (ref "C6") (pin "2") (pinfunction "2_2") (pintype "passive"))
      (node (ref "C7") (pin "2") (pinfunction "2_2") (pintype "passive"))
      (node (ref "C8") (pin "2") (pinfunction "2_2") (pintype "passive"))
      (node (ref "C9") (pin "2") (pinfunction "2_2") (pintype "passive"))
      (node (ref "GND") (pin "1") (pinfunction "P_1") (pintype "passive"))
      (node (ref "IC1") (pin "1") (pinfunction "VSS_1") (pintype "bidirectional"))
      (node (ref "IC10") (pin "7") (pinfunction "V-_7") (pintype "power_in"))
      (node (ref "IC2") (pin "2") (pinfunction "GND_2") (pintype "bidirectional"))
      (node (ref "IC2") (pin "EPAD") (pinfunction "GND_EPAD") (pintype "bidirectional"))
      (node (ref "IC3") (pin "2") (pinfunction "GND_2") (pintype "bidirectional"))
      (node (ref "IC3") (pin "EPAD") (pinfunction "GND_EPAD") (pintype "bidirectional"))
      (node (ref "IC4") (pin "20") (pinfunction "V-_20") (pintype "power_in"))
      (node (ref "IC4") (pin "25") (pinfunction "V-_25") (pintype "power_in"))
      (node (ref "IC4") (pin "41") (pinfunction "V-_41") (pintype "power_in"))
      (node (ref "IC4") (pin "9") (pinfunction "V-_9") (pintype "power_in"))
      (node (ref "IC5") (pin "12") (pinfunction "V-_12") (pintype "power_in"))
      (node (ref "IC5") (pin "16") (pinfunction "V-_16") (pintype "power_in"))
      (node (ref "IC5") (pin "18") (pinfunction "V-_18") (pintype "power_in"))
      (node (ref "IC5") (pin "21") (pinfunction "V-_21") (pintype "power_in"))
      (node (ref "IC5") (pin "27") (pinfunction "V-_27") (pintype "power_in"))
      (node (ref "IC5") (pin "3") (pinfunction "V-_3") (pintype "power_in"))
      (node (ref "IC5") (pin "30") (pinfunction "V-_30") (pintype "power_in"))
      (node (ref "IC5") (pin "31") (pinfunction "V-_31") (pintype "power_in"))
      (node (ref "IC5") (pin "32") (pinfunction "V-_32") (pintype "power_in"))
      (node (ref "IC5") (pin "6") (pinfunction "V-_6") (pintype "power_in"))
      (node (ref "IC5") (pin "7") (pinfunction "V-_7") (pintype "power_in"))
      (node (ref "IC5") (pin "PAD") (pinfunction "V-_PAD") (pintype "power_in"))
      (node (ref "IC6") (pin "13") (pinfunction "V-_13") (pintype "power_in"))
      (node (ref "IC6") (pin "PAD") (pinfunction "V-_PAD") (pintype "power_in"))
      (node (ref "IC7") (pin "1") (pinfunction "AISEN_1") (pintype "bidirectional"))
      (node (ref "IC7") (pin "11") (pinfunction "V-_11") (pintype "power_in"))
      (node (ref "IC7") (pin "4") (pinfunction "BISEN_4") (pintype "bidirectional"))
      (node (ref "IC7") (pin "PPAD") (pinfunction "V-_PPAD") (pintype "power_in"))
      (node (ref "IC8") (pin "1") (pinfunction "AISEN_1") (pintype "bidirectional"))
      (node (ref "IC8") (pin "11") (pinfunction "V-_11") (pintype "power_in"))
      (node (ref "IC8") (pin "4") (pinfunction "BISEN_4") (pintype "bidirectional"))
      (node (ref "IC8") (pin "PPAD") (pinfunction "V-_PPAD") (pintype "power_in"))
      (node (ref "IC9") (pin "1") (pinfunction "CLKIN_1") (pintype "bidirectional"))
      (node (ref "IC9") (pin "18") (pinfunction "V-_18") (pintype "power_in"))
      (node (ref "JP1") (pin "3") (pinfunction "3_3") (pintype "passive"))
      (node (ref "JP2") (pin "3") (pinfunction "3_3") (pintype "passive"))
      (node (ref "JP2") (pin "5") (pinfunction "5_5") (pintype "passive"))
      (node (ref "JP3") (pin "2") (pinfunction "2_2") (pintype "passive"))
      (node (ref "JP3") (pin "4") (pinfunction "4_4") (pintype "passive"))
      (node (ref "JP3") (pin "6") (pinfunction "6_6") (pintype "passive"))
      (node (ref "JP4") (pin "10") (pinfunction "DGND_10") (pintype "bidirectional"))
      (node (ref "JP4") (pin "19") (pinfunction "RESET_19") (pintype "bidirectional"))
      (node (ref "JP4") (pin "23") (pinfunction "AGND_23") (pintype "bidirectional"))
      (node (ref "OSC1") (pin "2") (pinfunction "GND_2") (pintype "bidirectional"))
      (node (ref "OSC2") (pin "2") (pinfunction "GND_2") (pintype "bidirectional"))
      (node (ref "OSC2") (pin "4") (pinfunction "GND_4") (pintype "bidirectional"))
      (node (ref "P2") (pin "1") (pinfunction "P_1") (pintype "passive"))
      (node (ref "R18") (pin "1") (pinfunction "1_1") (pintype "passive"))
      (node (ref "R2") (pin "1") (pinfunction "1_1") (pintype "passive"))
      (node (ref "R26") (pin "2") (pinfunction "2_2") (pintype "passive"))
      (node (ref "R27") (pin "2") (pinfunction "2_2") (pintype "passive"))
      (node (ref "R28") (pin "2") (pinfunction "2_2") (pintype "passive"))
      (node (ref "R6") (pin "2") (pinfunction "2_2") (pintype "passive"))
      (node (ref "R7") (pin "2") (pinfunction "2_2") (pintype "passive"))
    )
    (net (code "24") (name "GN_LED") (class "Default")
      (node (ref "IC4") (pin "28") (pinfunction "TDI/AN13/RB13_28") (pintype "bidirectional"))
      (node (ref "LED2") (pin "A") (pinfunction "A_A") (pintype "passive"))
    )
    (net (code "25") (name "IC3{slash}INT3{slash}RD10") (class "Default")
      (node (ref "IC4") (pin "44") (pinfunction "IC3/INT3/RD10_44") (pintype "bidirectional"))
      (node (ref "P16") (pin "1") (pinfunction "P_1") (pintype "passive"))
    )
    (net (code "26") (name "IMU_IRQ") (class "Default")
      (node (ref "IC4") (pin "42") (pinfunction "IC1/~{FLTA}/INT1/RD8_42") (pintype "bidirectional"))
      (node (ref "IC9") (pin "12") (pinfunction "INT_12") (pintype "bidirectional"))
    )
    (net (code "27") (name "LOWBATT_IRQ") (class "Default")
      (node (ref "IC1") (pin "2") (pinfunction "VOUT_2") (pintype "bidirectional"))
      (node (ref "IC4") (pin "43") (pinfunction "IC2/~{U1CTS}/~{FLTB}/INT2/RD9_43") (pintype "bidirectional"))
    )
    (net (code "28") (name "MOTOR_A_BEMF") (class "Default")
      (node (ref "C41") (pin "1") (pinfunction "1_1") (pintype "passive"))
      (node (ref "IC4") (pin "21") (pinfunction "~{U2CTS}/AN8/RB8_21") (pintype "bidirectional"))
      (node (ref "R29") (pin "2") (pinfunction "2_2") (pintype "passive"))
    )
    (net (code "29") (name "MOTOR_A_IN1") (class "Default")
      (node (ref "IC4") (pin "61") (pinfunction "PWM1H/RE1_61") (pintype "bidirectional"))
      (node (ref "IC7") (pin "14") (pinfunction "AIN1_14") (pintype "bidirectional"))
    )
    (net (code "30") (name "MOTOR_A_IN2") (class "Default")
      (node (ref "IC4") (pin "60") (pinfunction "PWM1L/RE0_60") (pintype "bidirectional"))
      (node (ref "IC7") (pin "13") (pinfunction "AIN2_13") (pintype "bidirectional"))
    )
    (net (code "31") (name "MOTOR_A_OUT1") (class "Default")
      (node (ref "C24") (pin "1") (pinfunction "1_1") (pintype "passive"))
      (node (ref "IC7") (pin "16") (pinfunction "AOUT1_16") (pintype "bidirectional"))
      (node (ref "P3") (pin "1") (pinfunction "P_1") (pintype "passive"))
      (node (ref "R9") (pin "1") (pinfunction "1_1") (pintype "passive"))
    )
    (net (code "32") (name "MOTOR_A_OUT2") (class "Default")
      (node (ref "C24") (pin "2") (pinfunction "2_2") (pintype "passive"))
      (node (ref "IC7") (pin "2") (pinfunction "AOUT2_2") (pintype "bidirectional"))
      (node (ref "P4") (pin "1") (pinfunction "P_1") (pintype "passive"))
      (node (ref "R10") (pin "1") (pinfunction "1_1") (pintype "passive"))
    )
    (net (code "33") (name "MOTOR_B_BEMF") (class "Default")
      (node (ref "C42") (pin "1") (pinfunction "1_1") (pintype "passive"))
      (node (ref "IC4") (pin "22") (pinfunction "AN9/RB9_22") (pintype "bidirectional"))
      (node (ref "R30") (pin "2") (pinfunction "2_2") (pintype "passive"))
    )
    (net (code "34") (name "MOTOR_B_IN1") (class "Default")
      (node (ref "IC4") (pin "63") (pinfunction "PWM2H/RE3_63") (pintype "bidirectional"))
      (node (ref "IC7") (pin "7") (pinfunction "BIN1_7") (pintype "bidirectional"))
    )
    (net (code "35") (name "MOTOR_B_IN2") (class "Default")
      (node (ref "IC4") (pin "62") (pinfunction "PWM2L/RE2_62") (pintype "bidirectional"))
      (node (ref "IC7") (pin "8") (pinfunction "BIN2_8") (pintype "bidirectional"))
    )
    (net (code "36") (name "MOTOR_B_OUT1") (class "Default")
      (node (ref "C25") (pin "1") (pinfunction "1_1") (pintype "passive"))
      (node (ref "IC7") (pin "5") (pinfunction "BOUT1_5") (pintype "bidirectional"))
      (node (ref "P5") (pin "1") (pinfunction "P_1") (pintype "passive"))
      (node (ref "R13") (pin "1") (pinfunction "1_1") (pintype "passive"))
    )
    (net (code "37") (name "MOTOR_B_OUT2") (class "Default")
      (node (ref "C25") (pin "2") (pinfunction "2_2") (pintype "passive"))
      (node (ref "IC7") (pin "3") (pinfunction "BOUT2_3") (pintype "bidirectional"))
      (node (ref "P6") (pin "1") (pinfunction "P_1") (pintype "passive"))
      (node (ref "R14") (pin "1") (pinfunction "1_1") (pintype "passive"))
    )
    (net (code "38") (name "MOTOR_C_BEMF") (class "Default")
      (node (ref "C43") (pin "1") (pinfunction "1_1") (pintype "passive"))
      (node (ref "IC4") (pin "23") (pinfunction "TMS/AN10/RB10_23") (pintype "bidirectional"))
      (node (ref "R31") (pin "2") (pinfunction "2_2") (pintype "passive"))
    )
    (net (code "39") (name "MOTOR_C_IN1") (class "Default")
      (node (ref "IC4") (pin "1") (pinfunction "PWM3H/RE5_1") (pintype "bidirectional"))
      (node (ref "IC8") (pin "14") (pinfunction "AIN1_14") (pintype "bidirectional"))
    )
    (net (code "40") (name "MOTOR_C_IN2") (class "Default")
      (node (ref "IC4") (pin "64") (pinfunction "PWM3L/RE4_64") (pintype "bidirectional"))
      (node (ref "IC8") (pin "13") (pinfunction "AIN2_13") (pintype "bidirectional"))
      (node (ref "PWM1") (pin "1") (pinfunction "P_1") (pintype "passive"))
    )
    (net (code "41") (name "MOTOR_C_OUT1") (class "Default")
      (node (ref "C27") (pin "1") (pinfunction "1_1") (pintype "passive"))
      (node (ref "IC8") (pin "16") (pinfunction "AOUT1_16") (pintype "bidirectional"))
      (node (ref "P7") (pin "1") (pinfunction "P_1") (pintype "passive"))
      (node (ref "R19") (pin "1") (pinfunction "1_1") (pintype "passive"))
    )
    (net (code "42") (name "MOTOR_C_OUT2") (class "Default")
      (node (ref "C27") (pin "2") (pinfunction "2_2") (pintype "passive"))
      (node (ref "IC8") (pin "2") (pinfunction "AOUT2_2") (pintype "bidirectional"))
      (node (ref "P8") (pin "1") (pinfunction "P_1") (pintype "passive"))
      (node (ref "R20") (pin "1") (pinfunction "1_1") (pintype "passive"))
    )
    (net (code "43") (name "MOTOR_D_BEMF") (class "Default")
      (node (ref "C44") (pin "1") (pinfunction "1_1") (pintype "passive"))
      (node (ref "IC4") (pin "24") (pinfunction "TDO/AN11/RB11_24") (pintype "bidirectional"))
      (node (ref "R32") (pin "2") (pinfunction "2_2") (pintype "passive"))
    )
    (net (code "44") (name "MOTOR_D_IN1") (class "Default")
      (node (ref "IC4") (pin "3") (pinfunction "PWM4H/RE7_3") (pintype "bidirectional"))
      (node (ref "IC8") (pin "7") (pinfunction "BIN1_7") (pintype "bidirectional"))
    )
    (net (code "45") (name "MOTOR_D_IN2") (class "Default")
      (node (ref "IC4") (pin "2") (pinfunction "PWM4L/RE6_2") (pintype "bidirectional"))
      (node (ref "IC8") (pin "8") (pinfunction "BIN2_8") (pintype "bidirectional"))
      (node (ref "PWM2") (pin "1") (pinfunction "P_1") (pintype "passive"))
    )
    (net (code "46") (name "MOTOR_D_OUT1") (class "Default")
      (node (ref "C28") (pin "1") (pinfunction "1_1") (pintype "passive"))
      (node (ref "IC8") (pin "5") (pinfunction "BOUT1_5") (pintype "bidirectional"))
      (node (ref "P9") (pin "1") (pinfunction "P_1") (pintype "passive"))
      (node (ref "R23") (pin "1") (pinfunction "1_1") (pintype "passive"))
    )
    (net (code "47") (name "MOTOR_D_OUT2") (class "Default")
      (node (ref "C28") (pin "2") (pinfunction "2_2") (pintype "passive"))
      (node (ref "IC8") (pin "3") (pinfunction "BOUT2_3") (pintype "bidirectional"))
      (node (ref "P10") (pin "1") (pinfunction "P_1") (pintype "passive"))
      (node (ref "R24") (pin "1") (pinfunction "1_1") (pintype "passive"))
    )
    (net (code "48") (name "Net-(ANT1-SIGNAL)") (class "Default")
      (node (ref "ANT1") (pin "A") (pinfunction "SIGNAL_A") (pintype "bidirectional"))
      (node (ref "B1") (pin "1") (pinfunction "UNBAL_1") (pintype "bidirectional"))
    )
    (net (code "49") (name "Net-(B1-BAL3)") (class "Default")
      (node (ref "B1") (pin "3") (pinfunction "BAL3_3") (pintype "bidirectional"))
      (node (ref "C17") (pin "1") (pinfunction "1_1") (pintype "passive"))
    )
    (net (code "50") (name "Net-(B1-BAL4)") (class "Default")
      (node (ref "B1") (pin "4") (pinfunction "BAL4_4") (pintype "bidirectional"))
      (node (ref "C16") (pin "2") (pinfunction "2_2") (pintype "passive"))
    )
    (net (code "51") (name "Net-(C22-Pad2)") (class "Default")
      (node (ref "C22") (pin "2") (pinfunction "2_2") (pintype "passive"))
      (node (ref "IC5") (pin "13") (pinfunction "V+_13") (pintype "power_in"))
      (node (ref "IC5") (pin "14") (pinfunction "V+_14") (pintype "power_in"))
    )
    (net (code "52") (name "Net-(IC4D-V+)") (class "Default")
      (node (ref "C10") (pin "1") (pinfunction "1_1") (pintype "passive"))
      (node (ref "IC4") (pin "19") (pinfunction "V+_19") (pintype "power_in"))
      (node (ref "L1") (pin "1") (pinfunction "1_1") (pintype "passive"))
    )
    (net (code "53") (name "Net-(IC4E-V+)") (class "Default")
      (node (ref "C15") (pin "1") (pinfunction "1_1") (pintype "passive"))
      (node (ref "IC4") (pin "56") (pinfunction "V+_56") (pintype "power_in"))
    )
    (net (code "54") (name "Net-(IC5A-V+)") (class "Default")
      (node (ref "C20") (pin "2") (pinfunction "2_2") (pintype "passive"))
      (node (ref "IC5") (pin "29") (pinfunction "V+_29") (pintype "power_in"))
    )
    (net (code "55") (name "Net-(IC5G-DIG2)") (class "Default")
      (node (ref "IC5") (pin "10") (pinfunction "DIG2_10") (pintype "bidirectional"))
      (node (ref "LED_TX") (pin "A") (pinfunction "A_A") (pintype "passive"))
    )
    (net (code "56") (name "Net-(IC5G-DIG3)") (class "Default")
      (node (ref "IC5") (pin "1") (pinfunction "DIG3_1") (pintype "bidirectional"))
      (node (ref "LED_RX") (pin "A") (pinfunction "A_A") (pintype "passive"))
    )
    (net (code "57") (name "Net-(IC5G-RFN)") (class "Default")
      (node (ref "C17") (pin "2") (pinfunction "2_2") (pintype "passive"))
      (node (ref "IC5") (pin "5") (pinfunction "RFN_5") (pintype "bidirectional"))
    )
    (net (code "58") (name "Net-(IC5G-RFP)") (class "Default")
      (node (ref "C16") (pin "1") (pinfunction "1_1") (pintype "passive"))
      (node (ref "IC5") (pin "4") (pinfunction "RFP_4") (pintype "bidirectional"))
    )
    (net (code "59") (name "Net-(IC5G-XTAL1)") (class "Default")
      (node (ref "C18") (pin "1") (pinfunction "1_1") (pintype "passive"))
      (node (ref "IC5") (pin "26") (pinfunction "XTAL1_26") (pintype "bidirectional"))
      (node (ref "OSC2") (pin "1") (pinfunction "IN/OUT_1") (pintype "bidirectional"))
    )
    (net (code "60") (name "Net-(IC5G-XTAL2)") (class "Default")
      (node (ref "C19") (pin "1") (pinfunction "1_1") (pintype "passive"))
      (node (ref "IC5") (pin "25") (pinfunction "XTAL2_25") (pintype "bidirectional"))
      (node (ref "OSC2") (pin "3") (pinfunction "OUT/IN_3") (pintype "bidirectional"))
    )
    (net (code "61") (name "Net-(IC6A-+IN)") (class "Default")
      (node (ref "IC6") (pin "3") (pinfunction "+IN_3") (pintype "input"))
      (node (ref "R10") (pin "2") (pinfunction "2_2") (pintype "passive"))
      (node (ref "R11") (pin "2") (pinfunction "2_2") (pintype "passive"))
    )
    (net (code "62") (name "Net-(IC6A--IN)") (class "Default")
      (node (ref "IC6") (pin "2") (pinfunction "-IN_2") (pintype "input"))
      (node (ref "R8") (pin "1") (pinfunction "1_1") (pintype "passive"))
      (node (ref "R9") (pin "2") (pinfunction "2_2") (pintype "passive"))
    )
    (net (code "63") (name "Net-(IC6A-OUT)") (class "Default")
      (node (ref "IC6") (pin "1") (pinfunction "OUT_1") (pintype "output"))
      (node (ref "R29") (pin "1") (pinfunction "1_1") (pintype "passive"))
      (node (ref "R8") (pin "2") (pinfunction "2_2") (pintype "passive"))
    )
    (net (code "64") (name "Net-(IC6B-+IN)") (class "Default")
      (node (ref "IC6") (pin "5") (pinfunction "+IN_5") (pintype "input"))
      (node (ref "R14") (pin "2") (pinfunction "2_2") (pintype "passive"))
      (node (ref "R15") (pin "2") (pinfunction "2_2") (pintype "passive"))
    )
    (net (code "65") (name "Net-(IC6B--IN)") (class "Default")
      (node (ref "IC6") (pin "6") (pinfunction "-IN_6") (pintype "input"))
      (node (ref "R12") (pin "1") (pinfunction "1_1") (pintype "passive"))
      (node (ref "R13") (pin "2") (pinfunction "2_2") (pintype "passive"))
    )
    (net (code "66") (name "Net-(IC6B-OUT)") (class "Default")
      (node (ref "IC6") (pin "7") (pinfunction "OUT_7") (pintype "output"))
      (node (ref "R12") (pin "2") (pinfunction "2_2") (pintype "passive"))
      (node (ref "R30") (pin "1") (pinfunction "1_1") (pintype "passive"))
    )
    (net (code "67") (name "Net-(IC6C-+IN)") (class "Default")
      (node (ref "IC6") (pin "12") (pinfunction "+IN_12") (pintype "input"))
      (node (ref "R20") (pin "2") (pinfunction "2_2") (pintype "passive"))
      (node (ref "R21") (pin "2") (pinfunction "2_2") (pintype "passive"))
    )
    (net (code "68") (name "Net-(IC6C--IN)") (class "Default")
      (node (ref "IC6") (pin "11") (pinfunction "-IN_11") (pintype "input"))
      (node (ref "R17") (pin "1") (pinfunction "1_1") (pintype "passive"))
      (node (ref "R19") (pin "2") (pinfunction "2_2") (pintype "passive"))
    )
    (net (code "69") (name "Net-(IC6C-OUT)") (class "Default")
      (node (ref "IC6") (pin "10") (pinfunction "OUT_10") (pintype "output"))
      (node (ref "R17") (pin "2") (pinfunction "2_2") (pintype "passive"))
      (node (ref "R31") (pin "1") (pinfunction "1_1") (pintype "passive"))
    )
    (net (code "70") (name "Net-(IC6D-+IN)") (class "Default")
      (node (ref "IC6") (pin "14") (pinfunction "+IN_14") (pintype "input"))
      (node (ref "R24") (pin "2") (pinfunction "2_2") (pintype "passive"))
      (node (ref "R25") (pin "2") (pinfunction "2_2") (pintype "passive"))
    )
    (net (code "71") (name "Net-(IC6D--IN)") (class "Default")
      (node (ref "IC6") (pin "15") (pinfunction "-IN_15") (pintype "input"))
      (node (ref "R22") (pin "1") (pinfunction "1_1") (pintype "passive"))
      (node (ref "R23") (pin "2") (pinfunction "2_2") (pintype "passive"))
    )
    (net (code "72") (name "Net-(IC6D-OUT)") (class "Default")
      (node (ref "IC6") (pin "16") (pinfunction "OUT_16") (pintype "output"))
      (node (ref "R22") (pin "2") (pinfunction "2_2") (pintype "passive"))
      (node (ref "R32") (pin "1") (pinfunction "1_1") (pintype "passive"))
    )
    (net (code "73") (name "Net-(IC7A-V+)") (class "Default")
      (node (ref "C31") (pin "2") (pinfunction "2_2") (pintype "passive"))
      (node (ref "IC7") (pin "9") (pinfunction "V+_9") (pintype "power_in"))
    )
    (net (code "74") (name "Net-(IC7B-V-)") (class "Default")
      (node (ref "C32") (pin "1") (pinfunction "1_1") (pintype "passive"))
      (node (ref "IC7") (pin "12") (pinfunction "V-_12") (pintype "power_in"))
    )
    (net (code "75") (name "Net-(IC8A-V+)") (class "Default")
      (node (ref "C34") (pin "2") (pinfunction "2_2") (pintype "passive"))
      (node (ref "IC8") (pin "9") (pinfunction "V+_9") (pintype "power_in"))
    )
    (net (code "76") (name "Net-(IC8B-V-)") (class "Default")
      (node (ref "C35") (pin "1") (pinfunction "1_1") (pintype "passive"))
      (node (ref "IC8") (pin "12") (pinfunction "V-_12") (pintype "power_in"))
    )
    (net (code "77") (name "Net-(IC9A-V-)") (class "Default")
      (node (ref "C38") (pin "2") (pinfunction "2_2") (pintype "passive"))
      (node (ref "IC9") (pin "20") (pinfunction "V-_20") (pintype "power_in"))
    )
    (net (code "78") (name "Net-(IC9B-V-)") (class "Default")
      (node (ref "C39") (pin "2") (pinfunction "2_2") (pintype "passive"))
      (node (ref "IC9") (pin "10") (pinfunction "V-_10") (pintype "power_in"))
    )
    (net (code "79") (name "Net-(LED1-PadC)") (class "Default")
      (node (ref "LED1") (pin "C") (pinfunction "C_C") (pintype "passive"))
      (node (ref "R26") (pin "1") (pinfunction "1_1") (pintype "passive"))
    )
    (net (code "80") (name "Net-(LED2-PadC)") (class "Default")
      (node (ref "LED2") (pin "C") (pinfunction "C_C") (pintype "passive"))
      (node (ref "R27") (pin "1") (pinfunction "1_1") (pintype "passive"))
    )
    (net (code "81") (name "Net-(LED3-PadC)") (class "Default")
      (node (ref "LED3") (pin "C") (pinfunction "C_C") (pintype "passive"))
      (node (ref "R28") (pin "1") (pinfunction "1_1") (pintype "passive"))
    )
    (net (code "82") (name "Net-(LED_RX-PadC)") (class "Default")
      (node (ref "LED_RX") (pin "C") (pinfunction "C_C") (pintype "passive"))
      (node (ref "R7") (pin "1") (pinfunction "1_1") (pintype "passive"))
    )
    (net (code "83") (name "Net-(LED_TX-PadC)") (class "Default")
      (node (ref "LED_TX") (pin "C") (pinfunction "C_C") (pintype "passive"))
      (node (ref "R6") (pin "1") (pinfunction "1_1") (pintype "passive"))
    )
    (net (code "84") (name "PGC") (class "Default")
      (node (ref "IC4") (pin "17") (pinfunction "PGEC1/AN6/OCFA/RB6_17") (pintype "bidirectional"))
      (node (ref "JP1") (pin "1") (pinfunction "1_1") (pintype "passive"))
    )
    (net (code "85") (name "PGD") (class "Default")
      (node (ref "IC4") (pin "18") (pinfunction "PGED1/AN7/RB7_18") (pintype "bidirectional"))
      (node (ref "JP1") (pin "2") (pinfunction "2_2") (pintype "passive"))
    )
    (net (code "86") (name "RADIO_IRQ") (class "Default")
      (node (ref "IC4") (pin "45") (pinfunction "IC4/INT4/RD11_45") (pintype "bidirectional"))
      (node (ref "IC5") (pin "24") (pinfunction "IRQ_24") (pintype "bidirectional"))
    )
    (net (code "87") (name "RADIO_SLP_TR") (class "Default")
      (node (ref "IC4") (pin "30") (pinfunction "AN15/OCFB/CN12/RB15_30") (pintype "bidirectional"))
      (node (ref "IC5") (pin "11") (pinfunction "SLP_TR_11") (pintype "bidirectional"))
    )
    (net (code "88") (name "RD_LED") (class "Default")
      (node (ref "IC4") (pin "27") (pinfunction "TCK/AN12/RB12_27") (pintype "bidirectional"))
      (node (ref "LED3") (pin "A") (pinfunction "A_A") (pintype "passive"))
    )
    (net (code "89") (name "SCK1") (class "Default")
      (node (ref "IC4") (pin "35") (pinfunction "~{U1RTS}/SCK1/INT0/RF6_35") (pintype "bidirectional"))
      (node (ref "IC5") (pin "19") (pinfunction "SCLK_19") (pintype "bidirectional"))
    )
    (net (code "90") (name "SCK2") (class "Default")
      (node (ref "IC10") (pin "2") (pinfunction "SCK_2") (pintype "bidirectional"))
      (node (ref "IC4") (pin "4") (pinfunction "SCK2/CN8/RG6_4") (pintype "bidirectional"))
      (node (ref "IC9") (pin "23") (pinfunction "SCL/SCLK_23") (pintype "bidirectional"))
    )
    (net (code "91") (name "SCL1") (class "Default")
      (node (ref "IC4") (pin "36") (pinfunction "SCL1/RG2_36") (pintype "bidirectional"))
      (node (ref "JP3") (pin "3") (pinfunction "3_3") (pintype "passive"))
      (node (ref "JP4") (pin "20") (pinfunction "SIO_C_20") (pintype "bidirectional"))
      (node (ref "R4") (pin "1") (pinfunction "1_1") (pintype "passive"))
    )
    (net (code "92") (name "SDA1") (class "Default")
      (node (ref "IC4") (pin "37") (pinfunction "SDA1/RG3_37") (pintype "bidirectional"))
      (node (ref "JP3") (pin "5") (pinfunction "5_5") (pintype "passive"))
      (node (ref "JP4") (pin "22") (pinfunction "SIO_D_22") (pintype "bidirectional"))
      (node (ref "R5") (pin "1") (pinfunction "1_1") (pintype "passive"))
    )
    (net (code "93") (name "SDI1") (class "Default")
      (node (ref "IC4") (pin "34") (pinfunction "U1RX/SDI1/RF2_34") (pintype "bidirectional"))
      (node (ref "IC5") (pin "20") (pinfunction "MISO_20") (pintype "bidirectional"))
    )
    (net (code "94") (name "SDI2") (class "Default")
      (node (ref "IC10") (pin "8") (pinfunction "SO_8") (pintype "bidirectional"))
      (node (ref "IC4") (pin "5") (pinfunction "SDI2/CN9/RG7_5") (pintype "bidirectional"))
      (node (ref "IC9") (pin "9") (pinfunction "AD0/SDO_9") (pintype "bidirectional"))
    )
    (net (code "95") (name "SDO1") (class "Default")
      (node (ref "IC4") (pin "33") (pinfunction "U1TX/SDO1/RF3_33") (pintype "bidirectional"))
      (node (ref "IC5") (pin "22") (pinfunction "MOSI_22") (pintype "bidirectional"))
    )
    (net (code "96") (name "SDO2") (class "Default")
      (node (ref "IC10") (pin "1") (pinfunction "SI_1") (pintype "bidirectional"))
      (node (ref "IC4") (pin "6") (pinfunction "SDO2/CN10/RG8_6") (pintype "bidirectional"))
      (node (ref "IC9") (pin "24") (pinfunction "SDA/SDI_24") (pintype "bidirectional"))
    )
    (net (code "97") (name "U2RX") (class "Default")
      (node (ref "IC4") (pin "31") (pinfunction "U2RX/SDA2/CN17/RF4_31") (pintype "bidirectional"))
      (node (ref "JP2") (pin "6") (pinfunction "6_6") (pintype "passive"))
    )
    (net (code "98") (name "U2TX") (class "Default")
      (node (ref "IC4") (pin "32") (pinfunction "U2TX/SCL2/CN18/RF5_32") (pintype "bidirectional"))
      (node (ref "JP2") (pin "4") (pinfunction "4_4") (pintype "passive"))
    )
    (net (code "99") (name "V_BATT") (class "Default")
      (node (ref "C3") (pin "1") (pinfunction "1_1") (pintype "passive"))
      (node (ref "C30") (pin "1") (pinfunction "1_1") (pintype "passive"))
      (node (ref "C31") (pin "1") (pinfunction "1_1") (pintype "passive"))
      (node (ref "C33") (pin "1") (pinfunction "1_1") (pintype "passive"))
      (node (ref "C34") (pin "1") (pinfunction "1_1") (pintype "passive"))
      (node (ref "C4") (pin "2") (pinfunction "2_2") (pintype "passive"))
      (node (ref "C5") (pin "2") (pinfunction "2_2") (pintype "passive"))
      (node (ref "IC1") (pin "3") (pinfunction "VIN_3") (pintype "bidirectional"))
      (node (ref "IC2") (pin "1") (pinfunction "VIN_1") (pintype "bidirectional"))
      (node (ref "IC2") (pin "3") (pinfunction "EN_3.0V_3") (pintype "bidirectional"))
      (node (ref "IC2") (pin "4") (pinfunction "EN_3.3V_4") (pintype "bidirectional"))
      (node (ref "IC3") (pin "1") (pinfunction "VIN_1") (pintype "bidirectional"))
      (node (ref "IC3") (pin "3") (pinfunction "EN_1.8V_3") (pintype "bidirectional"))
      (node (ref "IC3") (pin "4") (pinfunction "EN_2.5V_4") (pintype "bidirectional"))
      (node (ref "IC7") (pin "10") (pinfunction "V+_10") (pintype "power_in"))
      (node (ref "IC7") (pin "15") (pinfunction "~{SLEEP}_15") (pintype "bidirectional"))
      (node (ref "IC8") (pin "10") (pinfunction "V+_10") (pintype "power_in"))
      (node (ref "IC8") (pin "15") (pinfunction "~{SLEEP}_15") (pintype "bidirectional"))
      (node (ref "JP2") (pin "1") (pinfunction "1_1") (pintype "passive"))
      (node (ref "JP2") (pin "2") (pinfunction "2_2") (pintype "passive"))
      (node (ref "P1") (pin "1") (pinfunction "P_1") (pintype "passive"))
      (node (ref "R1") (pin "2") (pinfunction "2_2") (pintype "passive"))
    )
    (net (code "100") (name "V_REF") (class "Default")
      (node (ref "C26") (pin "1") (pinfunction "1_1") (pintype "passive"))
      (node (ref "R11") (pin "1") (pinfunction "1_1") (pintype "passive"))
      (node (ref "R15") (pin "1") (pinfunction "1_1") (pintype "passive"))
      (node (ref "R16") (pin "1") (pinfunction "1_1") (pintype "passive"))
      (node (ref "R18") (pin "2") (pinfunction "2_2") (pintype "passive"))
      (node (ref "R21") (pin "1") (pinfunction "1_1") (pintype "passive"))
      (node (ref "R25") (pin "1") (pinfunction "1_1") (pintype "passive"))
    )
    (net (code "101") (name "YW_LED") (class "Default")
      (node (ref "IC4") (pin "29") (pinfunction "~{U2RTS}/AN14/RB14_29") (pintype "bidirectional"))
      (node (ref "LED1") (pin "A") (pinfunction "A_A") (pintype "passive"))
    )
    (net (code "102") (name "unconnected-(B1-NC-Pad6)") (class "Default")
      (node (ref "B1") (pin "6") (pinfunction "NC_6") (pintype "bidirectional"))
    )
    (net (code "103") (name "unconnected-(IC5G-CLKM-Pad17)") (class "Default")
      (node (ref "IC5") (pin "17") (pinfunction "CLKM_17") (pintype "bidirectional"))
    )
    (net (code "104") (name "unconnected-(IC5G-DIG1-Pad9)") (class "Default")
      (node (ref "IC5") (pin "9") (pinfunction "DIG1_9") (pintype "bidirectional"))
    )
    (net (code "105") (name "unconnected-(IC5G-DIG4-Pad2)") (class "Default")
      (node (ref "IC5") (pin "2") (pinfunction "DIG4_2") (pintype "bidirectional"))
    )
    (net (code "106") (name "unconnected-(IC7D-~{FAULT}-Pad6)") (class "Default")
      (node (ref "IC7") (pin "6") (pinfunction "~{FAULT}_6") (pintype "bidirectional"))
    )
    (net (code "107") (name "unconnected-(IC8D-~{FAULT}-Pad6)") (class "Default")
      (node (ref "IC8") (pin "6") (pinfunction "~{FAULT}_6") (pintype "bidirectional"))
    )
    (net (code "108") (name "unconnected-(IC9D-AUX_CL-Pad7)") (class "Default")
      (node (ref "IC9") (pin "7") (pinfunction "AUX_CL_7") (pintype "bidirectional"))
    )
    (net (code "109") (name "unconnected-(IC9D-AUX_DA-Pad6)") (class "Default")
      (node (ref "IC9") (pin "6") (pinfunction "AUX_DA_6") (pintype "bidirectional"))
    )
    (net (code "110") (name "unconnected-(IC9D-CLKOUT-Pad22)") (class "Default")
      (node (ref "IC9") (pin "22") (pinfunction "CLKOUT_22") (pintype "bidirectional"))
    )
    (net (code "111") (name "unconnected-(JP1-Pad6)") (class "Default")
      (node (ref "JP1") (pin "6") (pinfunction "6_6") (pintype "passive"))
    )
    (net (code "112") (name "unconnected-(JP4-NC-Pad1)") (class "Default")
      (node (ref "JP4") (pin "1") (pinfunction "NC_1") (pintype "bidirectional"))
    )
    (net (code "113") (name "unconnected-(JP4-NC-Pad2)") (class "Default")
      (node (ref "JP4") (pin "2") (pinfunction "NC_2") (pintype "bidirectional"))
    )
    (net (code "114") (name "unconnected-(JP4-NC-Pad24)") (class "Default")
      (node (ref "JP4") (pin "24") (pinfunction "NC_24") (pintype "bidirectional"))
    )
    (net (code "115") (name "unconnected-(OSC1-EN-Pad1)") (class "Default")
      (node (ref "OSC1") (pin "1") (pinfunction "EN_1") (pintype "bidirectional"))
    )
    (net (code "116") (name "~{RESET}") (class "Default")
      (node (ref "IC10") (pin "3") (pinfunction "~{RESET}_3") (pintype "bidirectional"))
      (node (ref "IC4") (pin "7") (pinfunction "~{MCLR}_7") (pintype "input"))
      (node (ref "IC5") (pin "8") (pinfunction "~{RST}_8") (pintype "bidirectional"))
      (node (ref "JP1") (pin "5") (pinfunction "5_5") (pintype "passive"))
      (node (ref "R3") (pin "1") (pinfunction "1_1") (pintype "passive"))
    )
    (net (code "117") (name "~{SS1}") (class "Default")
      (node (ref "IC4") (pin "14") (pinfunction "AN2/~{SS1}/CN4/RB2_14") (pintype "bidirectional"))
      (node (ref "IC5") (pin "23") (pinfunction "~{SEL}_23") (pintype "bidirectional"))
    )
    (net (code "118") (name "~{SS2_1}") (class "Default")
      (node (ref "IC10") (pin "4") (pinfunction "~{CS}_4") (pintype "bidirectional"))
      (node (ref "IC4") (pin "8") (pinfunction "~{SS2}/CN11/RG9_8") (pintype "bidirectional"))
    )
    (net (code "119") (name "~{SS2_2}") (class "Default")
      (node (ref "IC4") (pin "40") (pinfunction "OSC2/CLKO/RC15_40") (pintype "bidirectional"))
      (node (ref "IC9") (pin "8") (pinfunction "~{CS}_8") (pintype "bidirectional"))
    )
  )
)
